# Sheet2.net
KiCad netlist of a schematic drawn in Altium Designer
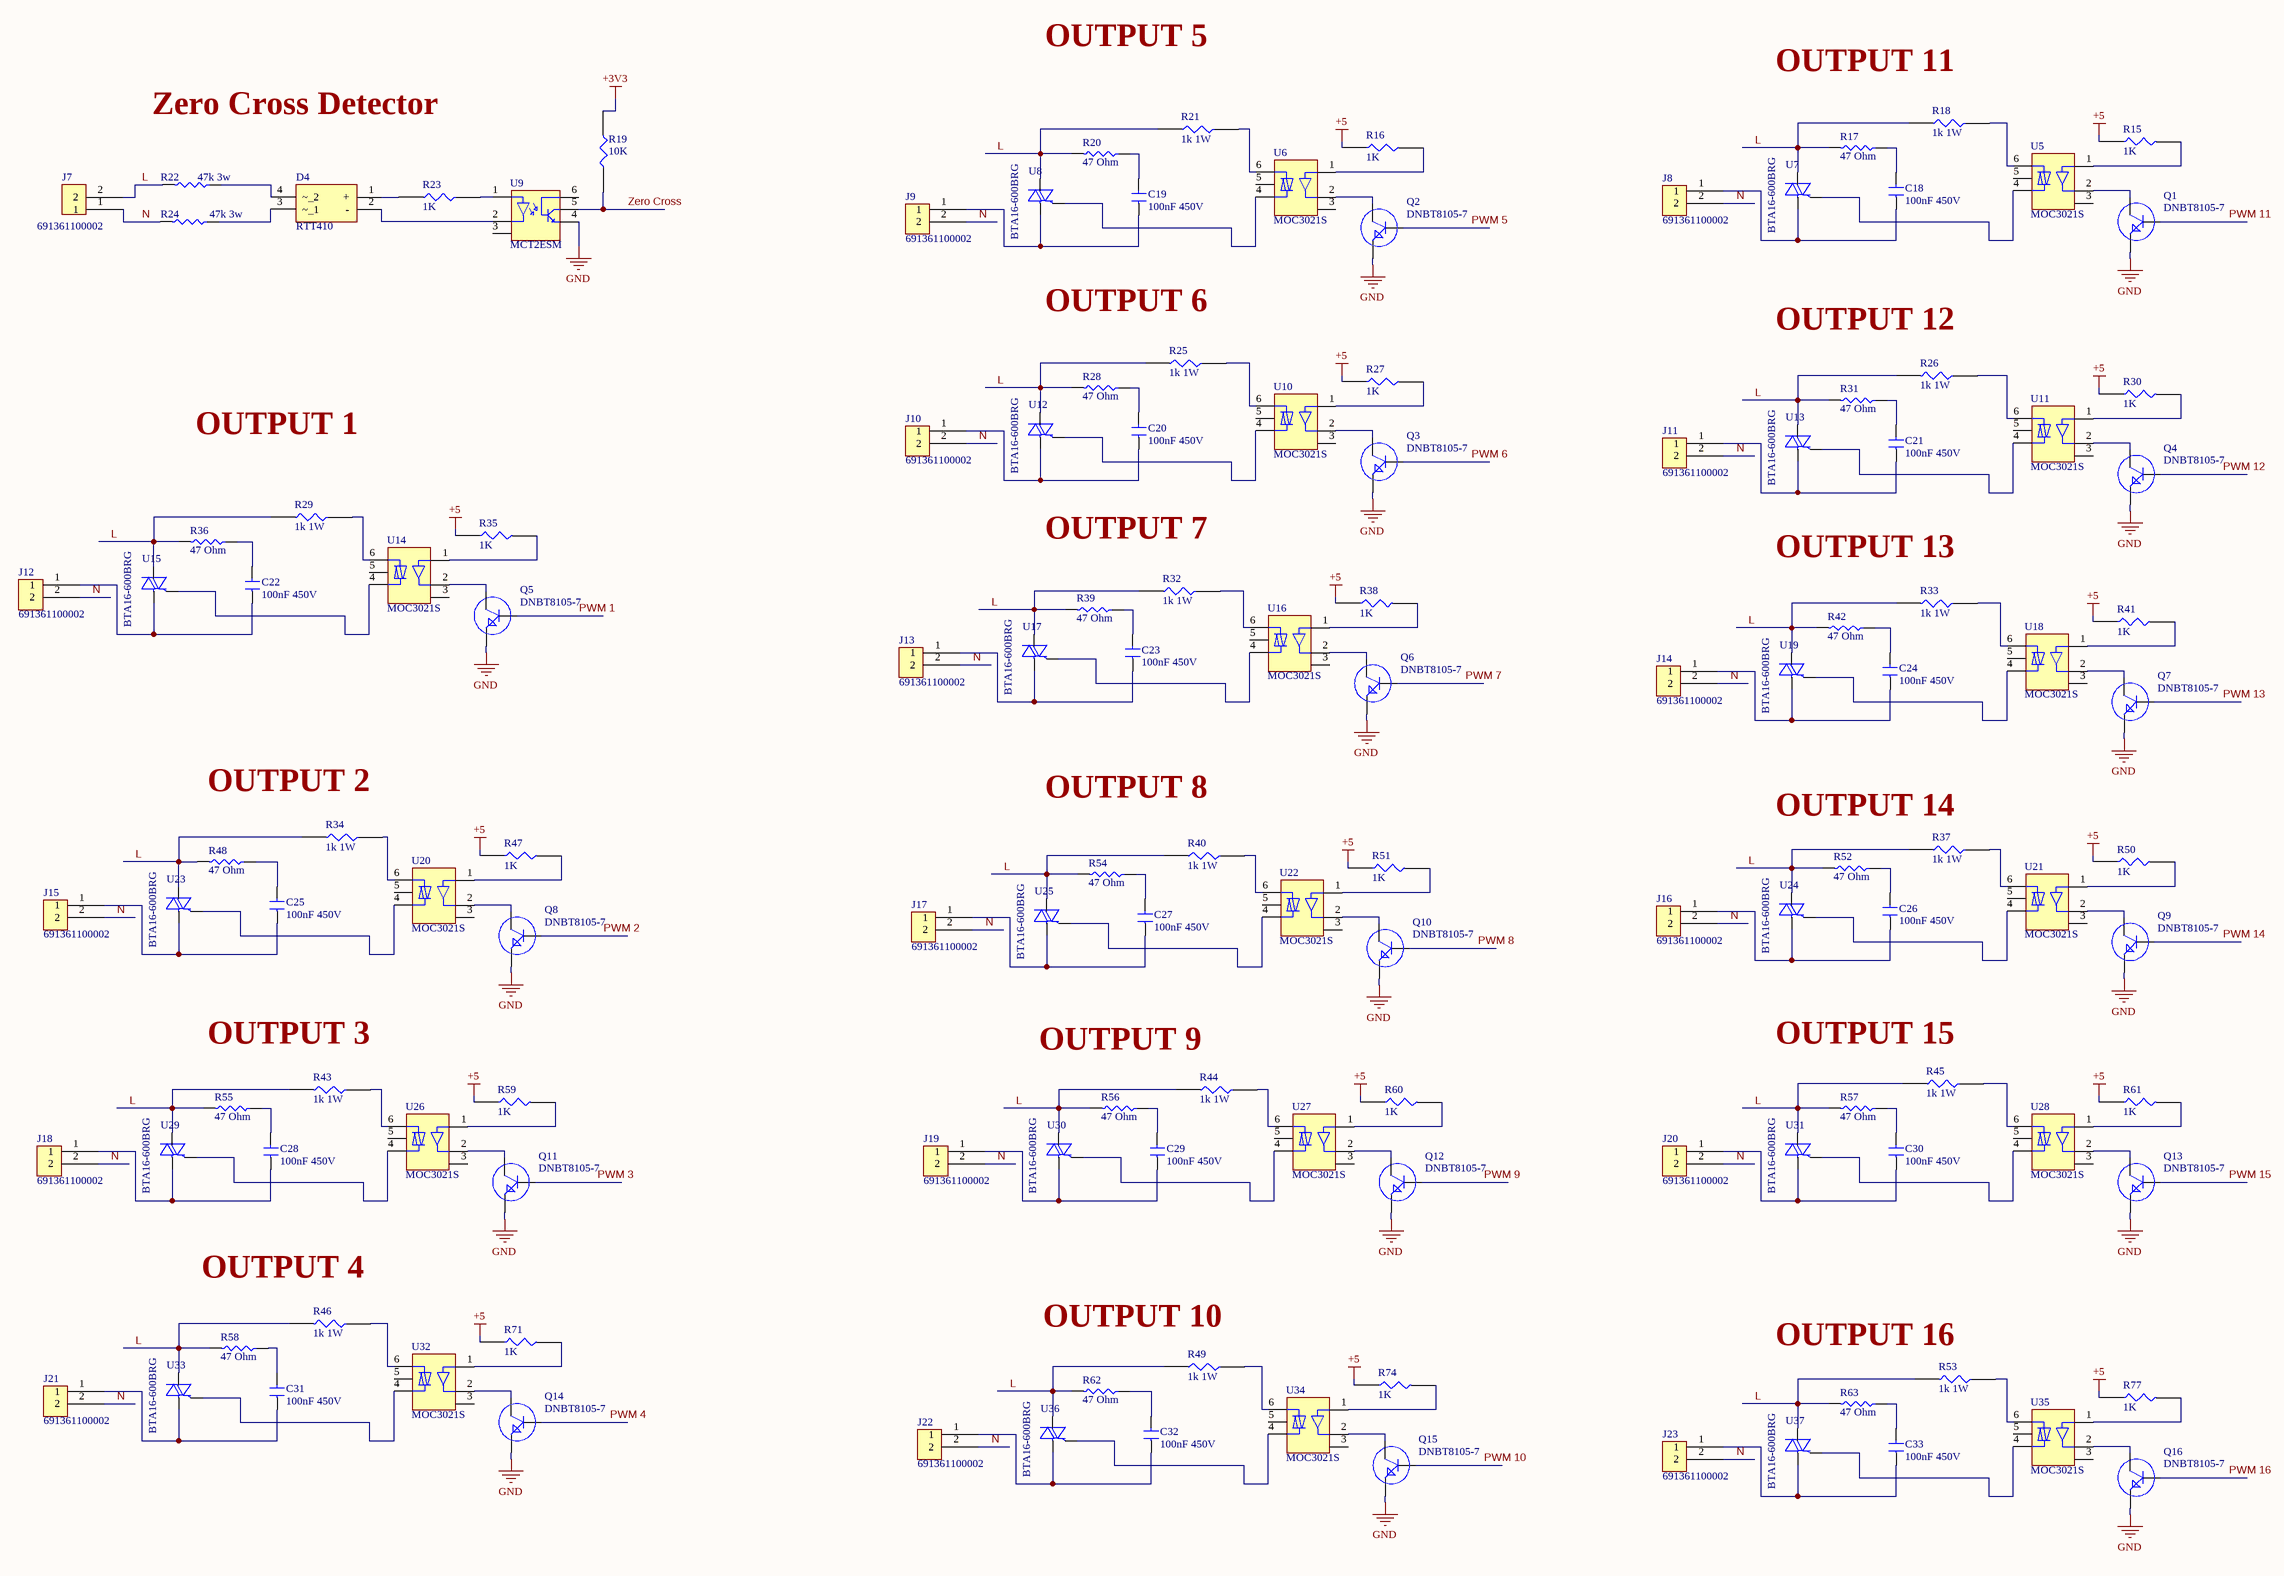
[diagram p0: Sheet2.SchDoc]

(export (version "E")
  (design (tool "Eeschema 10.0.6"))
  (components
    (comp (ref "C18")
      (value "100nF 450V")
      (footprint "CAP 1206")
      (description "Multilayer Ceramic Capacitor, 0.1 uF, 450 V, ± 10%, X7T, 1206 [3216 Metric]")
      (fields
        (field (name "MANUFACTURER") "TDK")
        (field (name "MANUFACTURER PART NUMBER") "CGA5L4X7T2W104K160AA")
      )
      (libsource (lib "Component Schematic Library V1") (part "Cap 100 nf 450V"))
    )
    (comp (ref "C19")
      (value "100nF 450V")
      (footprint "CAP 1206")
      (description "Multilayer Ceramic Capacitor, 0.1 uF, 450 V, ± 10%, X7T, 1206 [3216 Metric]")
      (fields
        (field (name "MANUFACTURER") "TDK")
        (field (name "MANUFACTURER PART NUMBER") "CGA5L4X7T2W104K160AA")
      )
      (libsource (lib "Component Schematic Library V1") (part "Cap 100 nf 450V"))
    )
    (comp (ref "C20")
      (value "100nF 450V")
      (footprint "CAP 1206")
      (description "Multilayer Ceramic Capacitor, 0.1 uF, 450 V, ± 10%, X7T, 1206 [3216 Metric]")
      (fields
        (field (name "MANUFACTURER") "TDK")
        (field (name "MANUFACTURER PART NUMBER") "CGA5L4X7T2W104K160AA")
      )
      (libsource (lib "Component Schematic Library V1") (part "Cap 100 nf 450V"))
    )
    (comp (ref "C21")
      (value "100nF 450V")
      (footprint "CAP 1206")
      (description "Multilayer Ceramic Capacitor, 0.1 uF, 450 V, ± 10%, X7T, 1206 [3216 Metric]")
      (fields
        (field (name "MANUFACTURER") "TDK")
        (field (name "MANUFACTURER PART NUMBER") "CGA5L4X7T2W104K160AA")
      )
      (libsource (lib "Component Schematic Library V1") (part "Cap 100 nf 450V"))
    )
    (comp (ref "C22")
      (value "100nF 450V")
      (footprint "CAP 1206")
      (description "Multilayer Ceramic Capacitor, 0.1 uF, 450 V, ± 10%, X7T, 1206 [3216 Metric]")
      (fields
        (field (name "MANUFACTURER") "TDK")
        (field (name "MANUFACTURER PART NUMBER") "CGA5L4X7T2W104K160AA")
      )
      (libsource (lib "Component Schematic Library V1") (part "Cap 100 nf 450V"))
    )
    (comp (ref "C23")
      (value "100nF 450V")
      (footprint "CAP 1206")
      (description "Multilayer Ceramic Capacitor, 0.1 uF, 450 V, ± 10%, X7T, 1206 [3216 Metric]")
      (fields
        (field (name "MANUFACTURER") "TDK")
        (field (name "MANUFACTURER PART NUMBER") "CGA5L4X7T2W104K160AA")
      )
      (libsource (lib "Component Schematic Library V1") (part "Cap 100 nf 450V"))
    )
    (comp (ref "C24")
      (value "100nF 450V")
      (footprint "CAP 1206")
      (description "Multilayer Ceramic Capacitor, 0.1 uF, 450 V, ± 10%, X7T, 1206 [3216 Metric]")
      (fields
        (field (name "MANUFACTURER") "TDK")
        (field (name "MANUFACTURER PART NUMBER") "CGA5L4X7T2W104K160AA")
      )
      (libsource (lib "Component Schematic Library V1") (part "Cap 100 nf 450V"))
    )
    (comp (ref "C25")
      (value "100nF 450V")
      (footprint "CAP 1206")
      (description "Multilayer Ceramic Capacitor, 0.1 uF, 450 V, ± 10%, X7T, 1206 [3216 Metric]")
      (fields
        (field (name "MANUFACTURER") "TDK")
        (field (name "MANUFACTURER PART NUMBER") "CGA5L4X7T2W104K160AA")
      )
      (libsource (lib "Component Schematic Library V1") (part "Cap 100 nf 450V"))
    )
    (comp (ref "C26")
      (value "100nF 450V")
      (footprint "CAP 1206")
      (description "Multilayer Ceramic Capacitor, 0.1 uF, 450 V, ± 10%, X7T, 1206 [3216 Metric]")
      (fields
        (field (name "MANUFACTURER") "TDK")
        (field (name "MANUFACTURER PART NUMBER") "CGA5L4X7T2W104K160AA")
      )
      (libsource (lib "Component Schematic Library V1") (part "Cap 100 nf 450V"))
    )
    (comp (ref "C27")
      (value "100nF 450V")
      (footprint "CAP 1206")
      (description "Multilayer Ceramic Capacitor, 0.1 uF, 450 V, ± 10%, X7T, 1206 [3216 Metric]")
      (fields
        (field (name "MANUFACTURER") "TDK")
        (field (name "MANUFACTURER PART NUMBER") "CGA5L4X7T2W104K160AA")
      )
      (libsource (lib "Component Schematic Library V1") (part "Cap 100 nf 450V"))
    )
    (comp (ref "C28")
      (value "100nF 450V")
      (footprint "CAP 1206")
      (description "Multilayer Ceramic Capacitor, 0.1 uF, 450 V, ± 10%, X7T, 1206 [3216 Metric]")
      (fields
        (field (name "MANUFACTURER") "TDK")
        (field (name "MANUFACTURER PART NUMBER") "CGA5L4X7T2W104K160AA")
      )
      (libsource (lib "Component Schematic Library V1") (part "Cap 100 nf 450V"))
    )
    (comp (ref "C29")
      (value "100nF 450V")
      (footprint "CAP 1206")
      (description "Multilayer Ceramic Capacitor, 0.1 uF, 450 V, ± 10%, X7T, 1206 [3216 Metric]")
      (fields
        (field (name "MANUFACTURER") "TDK")
        (field (name "MANUFACTURER PART NUMBER") "CGA5L4X7T2W104K160AA")
      )
      (libsource (lib "Component Schematic Library V1") (part "Cap 100 nf 450V"))
    )
    (comp (ref "C30")
      (value "100nF 450V")
      (footprint "CAP 1206")
      (description "Multilayer Ceramic Capacitor, 0.1 uF, 450 V, ± 10%, X7T, 1206 [3216 Metric]")
      (fields
        (field (name "MANUFACTURER") "TDK")
        (field (name "MANUFACTURER PART NUMBER") "CGA5L4X7T2W104K160AA")
      )
      (libsource (lib "Component Schematic Library V1") (part "Cap 100 nf 450V"))
    )
    (comp (ref "C31")
      (value "100nF 450V")
      (footprint "CAP 1206")
      (description "Multilayer Ceramic Capacitor, 0.1 uF, 450 V, ± 10%, X7T, 1206 [3216 Metric]")
      (fields
        (field (name "MANUFACTURER") "TDK")
        (field (name "MANUFACTURER PART NUMBER") "CGA5L4X7T2W104K160AA")
      )
      (libsource (lib "Component Schematic Library V1") (part "Cap 100 nf 450V"))
    )
    (comp (ref "C32")
      (value "100nF 450V")
      (footprint "CAP 1206")
      (description "Multilayer Ceramic Capacitor, 0.1 uF, 450 V, ± 10%, X7T, 1206 [3216 Metric]")
      (fields
        (field (name "MANUFACTURER") "TDK")
        (field (name "MANUFACTURER PART NUMBER") "CGA5L4X7T2W104K160AA")
      )
      (libsource (lib "Component Schematic Library V1") (part "Cap 100 nf 450V"))
    )
    (comp (ref "C33")
      (value "100nF 450V")
      (footprint "CAP 1206")
      (description "Multilayer Ceramic Capacitor, 0.1 uF, 450 V, ± 10%, X7T, 1206 [3216 Metric]")
      (fields
        (field (name "MANUFACTURER") "TDK")
        (field (name "MANUFACTURER PART NUMBER") "CGA5L4X7T2W104K160AA")
      )
      (libsource (lib "Component Schematic Library V1") (part "Cap 100 nf 450V"))
    )
    (comp (ref "D4")
      (value "RTT410")
      (footprint "RT410")
      (fields (field (name "MANUFACTURER") "Diodes"))
      (libsource (lib "Component Schematic Library V1") (part "RTT410"))
    )
    (comp (ref "J7")
      (value "691361100002")
      (footprint "Screw Terminal 3.5mm")
      (description "3611 Series 3.5mm Pitch Straight Pluggable Term Block; Plug; Cable Mount; 2 Way")
      (fields (field (name "MANUFACTURER") "Wurth Electronics") (field (name "VOLTAGE") "300V"))
      (libsource (lib "") (part "Screw Tarminal 3.5mm pitch_1"))
    )
    (comp (ref "J8")
      (value "691361100002")
      (footprint "Screw Terminal 3.5mm")
      (description "3611 Series 3.5mm Pitch Straight Pluggable Term Block; Plug; Cable Mount; 2 Way")
      (fields (field (name "MANUFACTURER") "Wurth Electronics") (field (name "VOLTAGE") "300V"))
      (libsource (lib "Component Schematic Library V1") (part "Screw Tarminal 3.5mm pitch"))
    )
    (comp (ref "J9")
      (value "691361100002")
      (footprint "Screw Terminal 3.5mm")
      (description "3611 Series 3.5mm Pitch Straight Pluggable Term Block; Plug; Cable Mount; 2 Way")
      (fields (field (name "MANUFACTURER") "Wurth Electronics") (field (name "VOLTAGE") "300V"))
      (libsource (lib "Component Schematic Library V1") (part "Screw Tarminal 3.5mm pitch"))
    )
    (comp (ref "J10")
      (value "691361100002")
      (footprint "Screw Terminal 3.5mm")
      (description "3611 Series 3.5mm Pitch Straight Pluggable Term Block; Plug; Cable Mount; 2 Way")
      (fields (field (name "MANUFACTURER") "Wurth Electronics") (field (name "VOLTAGE") "300V"))
      (libsource (lib "Component Schematic Library V1") (part "Screw Tarminal 3.5mm pitch"))
    )
    (comp (ref "J11")
      (value "691361100002")
      (footprint "Screw Terminal 3.5mm")
      (description "3611 Series 3.5mm Pitch Straight Pluggable Term Block; Plug; Cable Mount; 2 Way")
      (fields (field (name "MANUFACTURER") "Wurth Electronics") (field (name "VOLTAGE") "300V"))
      (libsource (lib "Component Schematic Library V1") (part "Screw Tarminal 3.5mm pitch"))
    )
    (comp (ref "J12")
      (value "691361100002")
      (footprint "Screw Terminal 3.5mm")
      (description "3611 Series 3.5mm Pitch Straight Pluggable Term Block; Plug; Cable Mount; 2 Way")
      (fields (field (name "MANUFACTURER") "Wurth Electronics") (field (name "VOLTAGE") "300V"))
      (libsource (lib "Component Schematic Library V1") (part "Screw Tarminal 3.5mm pitch"))
    )
    (comp (ref "J13")
      (value "691361100002")
      (footprint "Screw Terminal 3.5mm")
      (description "3611 Series 3.5mm Pitch Straight Pluggable Term Block; Plug; Cable Mount; 2 Way")
      (fields (field (name "MANUFACTURER") "Wurth Electronics") (field (name "VOLTAGE") "300V"))
      (libsource (lib "Component Schematic Library V1") (part "Screw Tarminal 3.5mm pitch"))
    )
    (comp (ref "J14")
      (value "691361100002")
      (footprint "Screw Terminal 3.5mm")
      (description "3611 Series 3.5mm Pitch Straight Pluggable Term Block; Plug; Cable Mount; 2 Way")
      (fields (field (name "MANUFACTURER") "Wurth Electronics") (field (name "VOLTAGE") "300V"))
      (libsource (lib "Component Schematic Library V1") (part "Screw Tarminal 3.5mm pitch"))
    )
    (comp (ref "J15")
      (value "691361100002")
      (footprint "Screw Terminal 3.5mm")
      (description "3611 Series 3.5mm Pitch Straight Pluggable Term Block; Plug; Cable Mount; 2 Way")
      (fields (field (name "MANUFACTURER") "Wurth Electronics") (field (name "VOLTAGE") "300V"))
      (libsource (lib "Component Schematic Library V1") (part "Screw Tarminal 3.5mm pitch"))
    )
    (comp (ref "J16")
      (value "691361100002")
      (footprint "Screw Terminal 3.5mm")
      (description "3611 Series 3.5mm Pitch Straight Pluggable Term Block; Plug; Cable Mount; 2 Way")
      (fields (field (name "MANUFACTURER") "Wurth Electronics") (field (name "VOLTAGE") "300V"))
      (libsource (lib "Component Schematic Library V1") (part "Screw Tarminal 3.5mm pitch"))
    )
    (comp (ref "J17")
      (value "691361100002")
      (footprint "Screw Terminal 3.5mm")
      (description "3611 Series 3.5mm Pitch Straight Pluggable Term Block; Plug; Cable Mount; 2 Way")
      (fields (field (name "MANUFACTURER") "Wurth Electronics") (field (name "VOLTAGE") "300V"))
      (libsource (lib "Component Schematic Library V1") (part "Screw Tarminal 3.5mm pitch"))
    )
    (comp (ref "J18")
      (value "691361100002")
      (footprint "Screw Terminal 3.5mm")
      (description "3611 Series 3.5mm Pitch Straight Pluggable Term Block; Plug; Cable Mount; 2 Way")
      (fields (field (name "MANUFACTURER") "Wurth Electronics") (field (name "VOLTAGE") "300V"))
      (libsource (lib "Component Schematic Library V1") (part "Screw Tarminal 3.5mm pitch"))
    )
    (comp (ref "J19")
      (value "691361100002")
      (footprint "Screw Terminal 3.5mm")
      (description "3611 Series 3.5mm Pitch Straight Pluggable Term Block; Plug; Cable Mount; 2 Way")
      (fields (field (name "MANUFACTURER") "Wurth Electronics") (field (name "VOLTAGE") "300V"))
      (libsource (lib "Component Schematic Library V1") (part "Screw Tarminal 3.5mm pitch"))
    )
    (comp (ref "J20")
      (value "691361100002")
      (footprint "Screw Terminal 3.5mm")
      (description "3611 Series 3.5mm Pitch Straight Pluggable Term Block; Plug; Cable Mount; 2 Way")
      (fields (field (name "MANUFACTURER") "Wurth Electronics") (field (name "VOLTAGE") "300V"))
      (libsource (lib "Component Schematic Library V1") (part "Screw Tarminal 3.5mm pitch"))
    )
    (comp (ref "J21")
      (value "691361100002")
      (footprint "Screw Terminal 3.5mm")
      (description "3611 Series 3.5mm Pitch Straight Pluggable Term Block; Plug; Cable Mount; 2 Way")
      (fields (field (name "MANUFACTURER") "Wurth Electronics") (field (name "VOLTAGE") "300V"))
      (libsource (lib "Component Schematic Library V1") (part "Screw Tarminal 3.5mm pitch"))
    )
    (comp (ref "J22")
      (value "691361100002")
      (footprint "Screw Terminal 3.5mm")
      (description "3611 Series 3.5mm Pitch Straight Pluggable Term Block; Plug; Cable Mount; 2 Way")
      (fields (field (name "MANUFACTURER") "Wurth Electronics") (field (name "VOLTAGE") "300V"))
      (libsource (lib "Component Schematic Library V1") (part "Screw Tarminal 3.5mm pitch"))
    )
    (comp (ref "J23")
      (value "691361100002")
      (footprint "Screw Terminal 3.5mm")
      (description "3611 Series 3.5mm Pitch Straight Pluggable Term Block; Plug; Cable Mount; 2 Way")
      (fields (field (name "MANUFACTURER") "Wurth Electronics") (field (name "VOLTAGE") "300V"))
      (libsource (lib "Component Schematic Library V1") (part "Screw Tarminal 3.5mm pitch"))
    )
    (comp (ref "Q1")
      (value "DNBT8105-7")
      (footprint "SOT 223 3")
      (description "TRANS NPN 60V 1A SOT23-3")
      (fields (field (name "MANUFACTURER") "Diodes Zetex"))
      (libsource (lib "Component Schematic Library V1") (part "NPN 1A"))
    )
    (comp (ref "Q2")
      (value "DNBT8105-7")
      (footprint "SOT 223 3")
      (description "TRANS NPN 60V 1A SOT23-3")
      (fields (field (name "MANUFACTURER") "Diodes Zetex"))
      (libsource (lib "Component Schematic Library V1") (part "NPN 1A"))
    )
    (comp (ref "Q3")
      (value "DNBT8105-7")
      (footprint "SOT 223 3")
      (description "TRANS NPN 60V 1A SOT23-3")
      (fields (field (name "MANUFACTURER") "Diodes Zetex"))
      (libsource (lib "Component Schematic Library V1") (part "NPN 1A"))
    )
    (comp (ref "Q4")
      (value "DNBT8105-7")
      (footprint "SOT 223 3")
      (description "TRANS NPN 60V 1A SOT23-3")
      (fields (field (name "MANUFACTURER") "Diodes Zetex"))
      (libsource (lib "Component Schematic Library V1") (part "NPN 1A"))
    )
    (comp (ref "Q5")
      (value "DNBT8105-7")
      (footprint "SOT 223 3")
      (description "TRANS NPN 60V 1A SOT23-3")
      (fields (field (name "MANUFACTURER") "Diodes Zetex"))
      (libsource (lib "Component Schematic Library V1") (part "NPN 1A"))
    )
    (comp (ref "Q6")
      (value "DNBT8105-7")
      (footprint "SOT 223 3")
      (description "TRANS NPN 60V 1A SOT23-3")
      (fields (field (name "MANUFACTURER") "Diodes Zetex"))
      (libsource (lib "Component Schematic Library V1") (part "NPN 1A"))
    )
    (comp (ref "Q7")
      (value "DNBT8105-7")
      (footprint "SOT 223 3")
      (description "TRANS NPN 60V 1A SOT23-3")
      (fields (field (name "MANUFACTURER") "Diodes Zetex"))
      (libsource (lib "Component Schematic Library V1") (part "NPN 1A"))
    )
    (comp (ref "Q8")
      (value "DNBT8105-7")
      (footprint "SOT 223 3")
      (description "TRANS NPN 60V 1A SOT23-3")
      (fields (field (name "MANUFACTURER") "Diodes Zetex"))
      (libsource (lib "Component Schematic Library V1") (part "NPN 1A"))
    )
    (comp (ref "Q9")
      (value "DNBT8105-7")
      (footprint "SOT 223 3")
      (description "TRANS NPN 60V 1A SOT23-3")
      (fields (field (name "MANUFACTURER") "Diodes Zetex"))
      (libsource (lib "Component Schematic Library V1") (part "NPN 1A"))
    )
    (comp (ref "Q10")
      (value "DNBT8105-7")
      (footprint "SOT 223 3")
      (description "TRANS NPN 60V 1A SOT23-3")
      (fields (field (name "MANUFACTURER") "Diodes Zetex"))
      (libsource (lib "Component Schematic Library V1") (part "NPN 1A"))
    )
    (comp (ref "Q11")
      (value "DNBT8105-7")
      (footprint "SOT 223 3")
      (description "TRANS NPN 60V 1A SOT23-3")
      (fields (field (name "MANUFACTURER") "Diodes Zetex"))
      (libsource (lib "Component Schematic Library V1") (part "NPN 1A"))
    )
    (comp (ref "Q12")
      (value "DNBT8105-7")
      (footprint "SOT 223 3")
      (description "TRANS NPN 60V 1A SOT23-3")
      (fields (field (name "MANUFACTURER") "Diodes Zetex"))
      (libsource (lib "Component Schematic Library V1") (part "NPN 1A"))
    )
    (comp (ref "Q13")
      (value "DNBT8105-7")
      (footprint "SOT 223 3")
      (description "TRANS NPN 60V 1A SOT23-3")
      (fields (field (name "MANUFACTURER") "Diodes Zetex"))
      (libsource (lib "Component Schematic Library V1") (part "NPN 1A"))
    )
    (comp (ref "Q14")
      (value "DNBT8105-7")
      (footprint "SOT 223 3")
      (description "TRANS NPN 60V 1A SOT23-3")
      (fields (field (name "MANUFACTURER") "Diodes Zetex"))
      (libsource (lib "Component Schematic Library V1") (part "NPN 1A"))
    )
    (comp (ref "Q15")
      (value "DNBT8105-7")
      (footprint "SOT 223 3")
      (description "TRANS NPN 60V 1A SOT23-3")
      (fields (field (name "MANUFACTURER") "Diodes Zetex"))
      (libsource (lib "Component Schematic Library V1") (part "NPN 1A"))
    )
    (comp (ref "Q16")
      (value "DNBT8105-7")
      (footprint "SOT 223 3")
      (description "TRANS NPN 60V 1A SOT23-3")
      (fields (field (name "MANUFACTURER") "Diodes Zetex"))
      (libsource (lib "Component Schematic Library V1") (part "NPN 1A"))
    )
    (comp (ref "R15")
      (value "1K")
      (footprint "R_0805")
      (description "贴片电阻 1000Ω ± 1.00% 0.125W ± 100ppm/℃ 0805")
      (fields
        (field (name "MANUFACTURER") "Yageo")
        (field (name "MANUFACTURER PART NUMBER") "RC0805FR-071KL")
      )
      (libsource (lib "Component Schematic Library V1") (part "RES_1_K_0805"))
    )
    (comp (ref "R16")
      (value "1K")
      (footprint "R_0805")
      (description "贴片电阻 1000Ω ± 1.00% 0.125W ± 100ppm/℃ 0805")
      (fields
        (field (name "MANUFACTURER") "Yageo")
        (field (name "MANUFACTURER PART NUMBER") "RC0805FR-071KL")
      )
      (libsource (lib "Component Schematic Library V1") (part "RES_1_K_0805"))
    )
    (comp (ref "R17")
      (value "47 Ohm")
      (footprint "R 1206")
      (description "Res Thick Film 1206 47 Ohm 1% 1/2W ±200ppm/°C Molded SMD Paper T/R")
      (fields
        (field (name "MANUFACTURER") "TE Connectivity")
        (field (name "MANUFACTURER PART NUMBER") "CRGH1206F47R")
      )
      (libsource (lib "Component Schematic Library V1") (part "Res 47 oHm 1/2 W"))
    )
    (comp (ref "R18")
      (value "1k 1W")
      (footprint "R_0805")
      (fields
        (field (name "MANUFACTURER") "TE Connectivity")
        (field (name "MANUFACTURER PART NUMBER") "RA73F2A1K0BTD")
      )
      (libsource (lib "Component Schematic Library V1") (part "Res 1K 1W"))
    )
    (comp (ref "R19")
      (value "10K")
      (footprint "R_0805")
      (description "贴片电阻 10000Ω ± 1.00% 0.125W ± 100ppm/℃ 0805")
      (fields
        (field (name "MANUFACTURER") "Yageo")
        (field (name "MANUFACTURER PART NUMBER") "RC0805FR-0710KL")
      )
      (libsource (lib "Component Schematic Library V1") (part "RES_10_K_0805"))
    )
    (comp (ref "R20")
      (value "47 Ohm")
      (footprint "R 1206")
      (description "Res Thick Film 1206 47 Ohm 1% 1/2W ±200ppm/°C Molded SMD Paper T/R")
      (fields
        (field (name "MANUFACTURER") "TE Connectivity")
        (field (name "MANUFACTURER PART NUMBER") "CRGH1206F47R")
      )
      (libsource (lib "Component Schematic Library V1") (part "Res 47 oHm 1/2 W"))
    )
    (comp (ref "R21")
      (value "1k 1W")
      (footprint "R_0805")
      (fields
        (field (name "MANUFACTURER") "TE Connectivity")
        (field (name "MANUFACTURER PART NUMBER") "RA73F2A1K0BTD")
      )
      (libsource (lib "Component Schematic Library V1") (part "Res 1K 1W"))
    )
    (comp (ref "R22")
      (value "47k 3w")
      (footprint "R 2512")
      (description "Res Thick Film 2512 47K Ohm 5% 3W ±100ppm/C Pad SMD T/R")
      (fields
        (field (name "MANUFACTURER") "TE Connectivity CGS")
        (field (name "MANUFACTURER PART NUMBER") "352247KJT")
      )
      (libsource (lib "Component Schematic Library V1") (part "RES 47K 3W SMD"))
    )
    (comp (ref "R23")
      (value "1K")
      (footprint "R_0805")
      (description "贴片电阻 1000Ω ± 1.00% 0.125W ± 100ppm/℃ 0805")
      (fields
        (field (name "MANUFACTURER") "Yageo")
        (field (name "MANUFACTURER PART NUMBER") "RC0805FR-071KL")
      )
      (libsource (lib "Component Schematic Library V1") (part "RES_1_K_0805"))
    )
    (comp (ref "R24")
      (value "47k 3w")
      (footprint "R 2512")
      (description "Res Thick Film 2512 47K Ohm 5% 3W ±100ppm/C Pad SMD T/R")
      (fields
        (field (name "MANUFACTURER") "TE Connectivity CGS")
        (field (name "MANUFACTURER PART NUMBER") "352247KJT")
      )
      (libsource (lib "Component Schematic Library V1") (part "RES 47K 3W SMD"))
    )
    (comp (ref "R25")
      (value "1k 1W")
      (footprint "R_0805")
      (fields
        (field (name "MANUFACTURER") "TE Connectivity")
        (field (name "MANUFACTURER PART NUMBER") "RA73F2A1K0BTD")
      )
      (libsource (lib "Component Schematic Library V1") (part "Res 1K 1W"))
    )
    (comp (ref "R26")
      (value "1k 1W")
      (footprint "R_0805")
      (fields
        (field (name "MANUFACTURER") "TE Connectivity")
        (field (name "MANUFACTURER PART NUMBER") "RA73F2A1K0BTD")
      )
      (libsource (lib "Component Schematic Library V1") (part "Res 1K 1W"))
    )
    (comp (ref "R27")
      (value "1K")
      (footprint "R_0805")
      (description "贴片电阻 1000Ω ± 1.00% 0.125W ± 100ppm/℃ 0805")
      (fields
        (field (name "MANUFACTURER") "Yageo")
        (field (name "MANUFACTURER PART NUMBER") "RC0805FR-071KL")
      )
      (libsource (lib "Component Schematic Library V1") (part "RES_1_K_0805"))
    )
    (comp (ref "R28")
      (value "47 Ohm")
      (footprint "R 1206")
      (description "Res Thick Film 1206 47 Ohm 1% 1/2W ±200ppm/°C Molded SMD Paper T/R")
      (fields
        (field (name "MANUFACTURER") "TE Connectivity")
        (field (name "MANUFACTURER PART NUMBER") "CRGH1206F47R")
      )
      (libsource (lib "Component Schematic Library V1") (part "Res 47 oHm 1/2 W"))
    )
    (comp (ref "R29")
      (value "1k 1W")
      (footprint "R_0805")
      (fields
        (field (name "MANUFACTURER") "TE Connectivity")
        (field (name "MANUFACTURER PART NUMBER") "RA73F2A1K0BTD")
      )
      (libsource (lib "Component Schematic Library V1") (part "Res 1K 1W"))
    )
    (comp (ref "R30")
      (value "1K")
      (footprint "R_0805")
      (description "贴片电阻 1000Ω ± 1.00% 0.125W ± 100ppm/℃ 0805")
      (fields
        (field (name "MANUFACTURER") "Yageo")
        (field (name "MANUFACTURER PART NUMBER") "RC0805FR-071KL")
      )
      (libsource (lib "Component Schematic Library V1") (part "RES_1_K_0805"))
    )
    (comp (ref "R31")
      (value "47 Ohm")
      (footprint "R 1206")
      (description "Res Thick Film 1206 47 Ohm 1% 1/2W ±200ppm/°C Molded SMD Paper T/R")
      (fields
        (field (name "MANUFACTURER") "TE Connectivity")
        (field (name "MANUFACTURER PART NUMBER") "CRGH1206F47R")
      )
      (libsource (lib "Component Schematic Library V1") (part "Res 47 oHm 1/2 W"))
    )
    (comp (ref "R32")
      (value "1k 1W")
      (footprint "R_0805")
      (fields
        (field (name "MANUFACTURER") "TE Connectivity")
        (field (name "MANUFACTURER PART NUMBER") "RA73F2A1K0BTD")
      )
      (libsource (lib "Component Schematic Library V1") (part "Res 1K 1W"))
    )
    (comp (ref "R33")
      (value "1k 1W")
      (footprint "R_0805")
      (fields
        (field (name "MANUFACTURER") "TE Connectivity")
        (field (name "MANUFACTURER PART NUMBER") "RA73F2A1K0BTD")
      )
      (libsource (lib "Component Schematic Library V1") (part "Res 1K 1W"))
    )
    (comp (ref "R34")
      (value "1k 1W")
      (footprint "R_0805")
      (fields
        (field (name "MANUFACTURER") "TE Connectivity")
        (field (name "MANUFACTURER PART NUMBER") "RA73F2A1K0BTD")
      )
      (libsource (lib "Component Schematic Library V1") (part "Res 1K 1W"))
    )
    (comp (ref "R35")
      (value "1K")
      (footprint "R_0805")
      (description "贴片电阻 1000Ω ± 1.00% 0.125W ± 100ppm/℃ 0805")
      (fields
        (field (name "MANUFACTURER") "Yageo")
        (field (name "MANUFACTURER PART NUMBER") "RC0805FR-071KL")
      )
      (libsource (lib "Component Schematic Library V1") (part "RES_1_K_0805"))
    )
    (comp (ref "R36")
      (value "47 Ohm")
      (footprint "R 1206")
      (description "Res Thick Film 1206 47 Ohm 1% 1/2W ±200ppm/°C Molded SMD Paper T/R")
      (fields
        (field (name "MANUFACTURER") "TE Connectivity")
        (field (name "MANUFACTURER PART NUMBER") "CRGH1206F47R")
      )
      (libsource (lib "Component Schematic Library V1") (part "Res 47 oHm 1/2 W"))
    )
    (comp (ref "R37")
      (value "1k 1W")
      (footprint "R_0805")
      (fields
        (field (name "MANUFACTURER") "TE Connectivity")
        (field (name "MANUFACTURER PART NUMBER") "RA73F2A1K0BTD")
      )
      (libsource (lib "Component Schematic Library V1") (part "Res 1K 1W"))
    )
    (comp (ref "R38")
      (value "1K")
      (footprint "R_0805")
      (description "贴片电阻 1000Ω ± 1.00% 0.125W ± 100ppm/℃ 0805")
      (fields
        (field (name "MANUFACTURER") "Yageo")
        (field (name "MANUFACTURER PART NUMBER") "RC0805FR-071KL")
      )
      (libsource (lib "Component Schematic Library V1") (part "RES_1_K_0805"))
    )
    (comp (ref "R39")
      (value "47 Ohm")
      (footprint "R 1206")
      (description "Res Thick Film 1206 47 Ohm 1% 1/2W ±200ppm/°C Molded SMD Paper T/R")
      (fields
        (field (name "MANUFACTURER") "TE Connectivity")
        (field (name "MANUFACTURER PART NUMBER") "CRGH1206F47R")
      )
      (libsource (lib "Component Schematic Library V1") (part "Res 47 oHm 1/2 W"))
    )
    (comp (ref "R40")
      (value "1k 1W")
      (footprint "R_0805")
      (fields
        (field (name "MANUFACTURER") "TE Connectivity")
        (field (name "MANUFACTURER PART NUMBER") "RA73F2A1K0BTD")
      )
      (libsource (lib "Component Schematic Library V1") (part "Res 1K 1W"))
    )
    (comp (ref "R41")
      (value "1K")
      (footprint "R_0805")
      (description "贴片电阻 1000Ω ± 1.00% 0.125W ± 100ppm/℃ 0805")
      (fields
        (field (name "MANUFACTURER") "Yageo")
        (field (name "MANUFACTURER PART NUMBER") "RC0805FR-071KL")
      )
      (libsource (lib "Component Schematic Library V1") (part "RES_1_K_0805"))
    )
    (comp (ref "R42")
      (value "47 Ohm")
      (footprint "R 1206")
      (description "Res Thick Film 1206 47 Ohm 1% 1/2W ±200ppm/°C Molded SMD Paper T/R")
      (fields
        (field (name "MANUFACTURER") "TE Connectivity")
        (field (name "MANUFACTURER PART NUMBER") "CRGH1206F47R")
      )
      (libsource (lib "Component Schematic Library V1") (part "Res 47 oHm 1/2 W"))
    )
    (comp (ref "R43")
      (value "1k 1W")
      (footprint "R_0805")
      (fields
        (field (name "MANUFACTURER") "TE Connectivity")
        (field (name "MANUFACTURER PART NUMBER") "RA73F2A1K0BTD")
      )
      (libsource (lib "Component Schematic Library V1") (part "Res 1K 1W"))
    )
    (comp (ref "R44")
      (value "1k 1W")
      (footprint "R_0805")
      (fields
        (field (name "MANUFACTURER") "TE Connectivity")
        (field (name "MANUFACTURER PART NUMBER") "RA73F2A1K0BTD")
      )
      (libsource (lib "Component Schematic Library V1") (part "Res 1K 1W"))
    )
    (comp (ref "R45")
      (value "1k 1W")
      (footprint "R_0805")
      (fields
        (field (name "MANUFACTURER") "TE Connectivity")
        (field (name "MANUFACTURER PART NUMBER") "RA73F2A1K0BTD")
      )
      (libsource (lib "Component Schematic Library V1") (part "Res 1K 1W"))
    )
    (comp (ref "R46")
      (value "1k 1W")
      (footprint "R_0805")
      (fields
        (field (name "MANUFACTURER") "TE Connectivity")
        (field (name "MANUFACTURER PART NUMBER") "RA73F2A1K0BTD")
      )
      (libsource (lib "Component Schematic Library V1") (part "Res 1K 1W"))
    )
    (comp (ref "R47")
      (value "1K")
      (footprint "R_0805")
      (description "贴片电阻 1000Ω ± 1.00% 0.125W ± 100ppm/℃ 0805")
      (fields
        (field (name "MANUFACTURER") "Yageo")
        (field (name "MANUFACTURER PART NUMBER") "RC0805FR-071KL")
      )
      (libsource (lib "Component Schematic Library V1") (part "RES_1_K_0805"))
    )
    (comp (ref "R48")
      (value "47 Ohm")
      (footprint "R 1206")
      (description "Res Thick Film 1206 47 Ohm 1% 1/2W ±200ppm/°C Molded SMD Paper T/R")
      (fields
        (field (name "MANUFACTURER") "TE Connectivity")
        (field (name "MANUFACTURER PART NUMBER") "CRGH1206F47R")
      )
      (libsource (lib "Component Schematic Library V1") (part "Res 47 oHm 1/2 W"))
    )
    (comp (ref "R49")
      (value "1k 1W")
      (footprint "R_0805")
      (fields
        (field (name "MANUFACTURER") "TE Connectivity")
        (field (name "MANUFACTURER PART NUMBER") "RA73F2A1K0BTD")
      )
      (libsource (lib "Component Schematic Library V1") (part "Res 1K 1W"))
    )
    (comp (ref "R50")
      (value "1K")
      (footprint "R_0805")
      (description "贴片电阻 1000Ω ± 1.00% 0.125W ± 100ppm/℃ 0805")
      (fields
        (field (name "MANUFACTURER") "Yageo")
        (field (name "MANUFACTURER PART NUMBER") "RC0805FR-071KL")
      )
      (libsource (lib "Component Schematic Library V1") (part "RES_1_K_0805"))
    )
    (comp (ref "R51")
      (value "1K")
      (footprint "R_0805")
      (description "贴片电阻 1000Ω ± 1.00% 0.125W ± 100ppm/℃ 0805")
      (fields
        (field (name "MANUFACTURER") "Yageo")
        (field (name "MANUFACTURER PART NUMBER") "RC0805FR-071KL")
      )
      (libsource (lib "Component Schematic Library V1") (part "RES_1_K_0805"))
    )
    (comp (ref "R52")
      (value "47 Ohm")
      (footprint "R 1206")
      (description "Res Thick Film 1206 47 Ohm 1% 1/2W ±200ppm/°C Molded SMD Paper T/R")
      (fields
        (field (name "MANUFACTURER") "TE Connectivity")
        (field (name "MANUFACTURER PART NUMBER") "CRGH1206F47R")
      )
      (libsource (lib "Component Schematic Library V1") (part "Res 47 oHm 1/2 W"))
    )
    (comp (ref "R53")
      (value "1k 1W")
      (footprint "R_0805")
      (fields
        (field (name "MANUFACTURER") "TE Connectivity")
        (field (name "MANUFACTURER PART NUMBER") "RA73F2A1K0BTD")
      )
      (libsource (lib "Component Schematic Library V1") (part "Res 1K 1W"))
    )
    (comp (ref "R54")
      (value "47 Ohm")
      (footprint "R 1206")
      (description "Res Thick Film 1206 47 Ohm 1% 1/2W ±200ppm/°C Molded SMD Paper T/R")
      (fields
        (field (name "MANUFACTURER") "TE Connectivity")
        (field (name "MANUFACTURER PART NUMBER") "CRGH1206F47R")
      )
      (libsource (lib "Component Schematic Library V1") (part "Res 47 oHm 1/2 W"))
    )
    (comp (ref "R55")
      (value "47 Ohm")
      (footprint "R 1206")
      (description "Res Thick Film 1206 47 Ohm 1% 1/2W ±200ppm/°C Molded SMD Paper T/R")
      (fields
        (field (name "MANUFACTURER") "TE Connectivity")
        (field (name "MANUFACTURER PART NUMBER") "CRGH1206F47R")
      )
      (libsource (lib "Component Schematic Library V1") (part "Res 47 oHm 1/2 W"))
    )
    (comp (ref "R56")
      (value "47 Ohm")
      (footprint "R 1206")
      (description "Res Thick Film 1206 47 Ohm 1% 1/2W ±200ppm/°C Molded SMD Paper T/R")
      (fields
        (field (name "MANUFACTURER") "TE Connectivity")
        (field (name "MANUFACTURER PART NUMBER") "CRGH1206F47R")
      )
      (libsource (lib "Component Schematic Library V1") (part "Res 47 oHm 1/2 W"))
    )
    (comp (ref "R57")
      (value "47 Ohm")
      (footprint "R 1206")
      (description "Res Thick Film 1206 47 Ohm 1% 1/2W ±200ppm/°C Molded SMD Paper T/R")
      (fields
        (field (name "MANUFACTURER") "TE Connectivity")
        (field (name "MANUFACTURER PART NUMBER") "CRGH1206F47R")
      )
      (libsource (lib "Component Schematic Library V1") (part "Res 47 oHm 1/2 W"))
    )
    (comp (ref "R58")
      (value "47 Ohm")
      (footprint "R 1206")
      (description "Res Thick Film 1206 47 Ohm 1% 1/2W ±200ppm/°C Molded SMD Paper T/R")
      (fields
        (field (name "MANUFACTURER") "TE Connectivity")
        (field (name "MANUFACTURER PART NUMBER") "CRGH1206F47R")
      )
      (libsource (lib "Component Schematic Library V1") (part "Res 47 oHm 1/2 W"))
    )
    (comp (ref "R59")
      (value "1K")
      (footprint "R_0805")
      (description "贴片电阻 1000Ω ± 1.00% 0.125W ± 100ppm/℃ 0805")
      (fields
        (field (name "MANUFACTURER") "Yageo")
        (field (name "MANUFACTURER PART NUMBER") "RC0805FR-071KL")
      )
      (libsource (lib "Component Schematic Library V1") (part "RES_1_K_0805"))
    )
    (comp (ref "R60")
      (value "1K")
      (footprint "R_0805")
      (description "贴片电阻 1000Ω ± 1.00% 0.125W ± 100ppm/℃ 0805")
      (fields
        (field (name "MANUFACTURER") "Yageo")
        (field (name "MANUFACTURER PART NUMBER") "RC0805FR-071KL")
      )
      (libsource (lib "Component Schematic Library V1") (part "RES_1_K_0805"))
    )
    (comp (ref "R61")
      (value "1K")
      (footprint "R_0805")
      (description "贴片电阻 1000Ω ± 1.00% 0.125W ± 100ppm/℃ 0805")
      (fields
        (field (name "MANUFACTURER") "Yageo")
        (field (name "MANUFACTURER PART NUMBER") "RC0805FR-071KL")
      )
      (libsource (lib "Component Schematic Library V1") (part "RES_1_K_0805"))
    )
    (comp (ref "R62")
      (value "47 Ohm")
      (footprint "R 1206")
      (description "Res Thick Film 1206 47 Ohm 1% 1/2W ±200ppm/°C Molded SMD Paper T/R")
      (fields
        (field (name "MANUFACTURER") "TE Connectivity")
        (field (name "MANUFACTURER PART NUMBER") "CRGH1206F47R")
      )
      (libsource (lib "Component Schematic Library V1") (part "Res 47 oHm 1/2 W"))
    )
    (comp (ref "R63")
      (value "47 Ohm")
      (footprint "R 1206")
      (description "Res Thick Film 1206 47 Ohm 1% 1/2W ±200ppm/°C Molded SMD Paper T/R")
      (fields
        (field (name "MANUFACTURER") "TE Connectivity")
        (field (name "MANUFACTURER PART NUMBER") "CRGH1206F47R")
      )
      (libsource (lib "Component Schematic Library V1") (part "Res 47 oHm 1/2 W"))
    )
    (comp (ref "R71")
      (value "1K")
      (footprint "R_0805")
      (description "贴片电阻 1000Ω ± 1.00% 0.125W ± 100ppm/℃ 0805")
      (fields
        (field (name "MANUFACTURER") "Yageo")
        (field (name "MANUFACTURER PART NUMBER") "RC0805FR-071KL")
      )
      (libsource (lib "Component Schematic Library V1") (part "RES_1_K_0805"))
    )
    (comp (ref "R74")
      (value "1K")
      (footprint "R_0805")
      (description "贴片电阻 1000Ω ± 1.00% 0.125W ± 100ppm/℃ 0805")
      (fields
        (field (name "MANUFACTURER") "Yageo")
        (field (name "MANUFACTURER PART NUMBER") "RC0805FR-071KL")
      )
      (libsource (lib "Component Schematic Library V1") (part "RES_1_K_0805"))
    )
    (comp (ref "R77")
      (value "1K")
      (footprint "R_0805")
      (description "贴片电阻 1000Ω ± 1.00% 0.125W ± 100ppm/℃ 0805")
      (fields
        (field (name "MANUFACTURER") "Yageo")
        (field (name "MANUFACTURER PART NUMBER") "RC0805FR-071KL")
      )
      (libsource (lib "Component Schematic Library V1") (part "RES_1_K_0805"))
    )
    (comp (ref "U5")
      (value "MOC3021S")
      (footprint "SMD 6")
      (description "MOC302x Series 1 Channel 400 V 5000 Vrms Surface Mount Triac Optocoupler - SMD-6")
      (fields (field (name "MANUFACTURER") "Vishay Lite-On"))
      (libsource (lib "Component Schematic Library V1") (part "MOC3021S"))
    )
    (comp (ref "U6")
      (value "MOC3021S")
      (footprint "SMD 6")
      (description "MOC302x Series 1 Channel 400 V 5000 Vrms Surface Mount Triac Optocoupler - SMD-6")
      (fields (field (name "MANUFACTURER") "Vishay Lite-On"))
      (libsource (lib "Component Schematic Library V1") (part "MOC3021S"))
    )
    (comp (ref "U7")
      (value "BTA16-600BRG")
      (footprint "BAT16")
      (description "TRIAC Standard 600V 16A Through Hole TO-220AB")
      (libsource (lib "Component Schematic Library V1") (part "Triac"))
    )
    (comp (ref "U8")
      (value "BTA16-600BRG")
      (footprint "BAT16")
      (description "TRIAC Standard 600V 16A Through Hole TO-220AB")
      (libsource (lib "Component Schematic Library V1") (part "Triac"))
    )
    (comp (ref "U9")
      (value "MCT2ESM")
      (footprint "SMD 6")
      (description "DC-IN 1-CH Transistor With Base DC-OUT 6-Pin PDIP SMD")
      (fields (field (name "MANUFACTURER") "ON Semiconductor / Fairchild"))
      (libsource (lib "Component Schematic Library V1") (part "MCT2ESM"))
    )
    (comp (ref "U10")
      (value "MOC3021S")
      (footprint "SMD 6")
      (description "MOC302x Series 1 Channel 400 V 5000 Vrms Surface Mount Triac Optocoupler - SMD-6")
      (fields (field (name "MANUFACTURER") "Vishay Lite-On"))
      (libsource (lib "Component Schematic Library V1") (part "MOC3021S"))
    )
    (comp (ref "U11")
      (value "MOC3021S")
      (footprint "SMD 6")
      (description "MOC302x Series 1 Channel 400 V 5000 Vrms Surface Mount Triac Optocoupler - SMD-6")
      (fields (field (name "MANUFACTURER") "Vishay Lite-On"))
      (libsource (lib "Component Schematic Library V1") (part "MOC3021S"))
    )
    (comp (ref "U12")
      (value "BTA16-600BRG")
      (footprint "BAT16")
      (description "TRIAC Standard 600V 16A Through Hole TO-220AB")
      (libsource (lib "Component Schematic Library V1") (part "Triac"))
    )
    (comp (ref "U13")
      (value "BTA16-600BRG")
      (footprint "BAT16")
      (description "TRIAC Standard 600V 16A Through Hole TO-220AB")
      (libsource (lib "Component Schematic Library V1") (part "Triac"))
    )
    (comp (ref "U14")
      (value "MOC3021S")
      (footprint "SMD 6")
      (description "MOC302x Series 1 Channel 400 V 5000 Vrms Surface Mount Triac Optocoupler - SMD-6")
      (fields (field (name "MANUFACTURER") "Vishay Lite-On"))
      (libsource (lib "Component Schematic Library V1") (part "MOC3021S"))
    )
    (comp (ref "U15")
      (value "BTA16-600BRG")
      (footprint "BAT16")
      (description "TRIAC Standard 600V 16A Through Hole TO-220AB")
      (libsource (lib "Component Schematic Library V1") (part "Triac"))
    )
    (comp (ref "U16")
      (value "MOC3021S")
      (footprint "SMD 6")
      (description "MOC302x Series 1 Channel 400 V 5000 Vrms Surface Mount Triac Optocoupler - SMD-6")
      (fields (field (name "MANUFACTURER") "Vishay Lite-On"))
      (libsource (lib "Component Schematic Library V1") (part "MOC3021S"))
    )
    (comp (ref "U17")
      (value "BTA16-600BRG")
      (footprint "BAT16")
      (description "TRIAC Standard 600V 16A Through Hole TO-220AB")
      (libsource (lib "Component Schematic Library V1") (part "Triac"))
    )
    (comp (ref "U18")
      (value "MOC3021S")
      (footprint "SMD 6")
      (description "MOC302x Series 1 Channel 400 V 5000 Vrms Surface Mount Triac Optocoupler - SMD-6")
      (fields (field (name "MANUFACTURER") "Vishay Lite-On"))
      (libsource (lib "Component Schematic Library V1") (part "MOC3021S"))
    )
    (comp (ref "U19")
      (value "BTA16-600BRG")
      (footprint "BAT16")
      (description "TRIAC Standard 600V 16A Through Hole TO-220AB")
      (libsource (lib "Component Schematic Library V1") (part "Triac"))
    )
    (comp (ref "U20")
      (value "MOC3021S")
      (footprint "SMD 6")
      (description "MOC302x Series 1 Channel 400 V 5000 Vrms Surface Mount Triac Optocoupler - SMD-6")
      (fields (field (name "MANUFACTURER") "Vishay Lite-On"))
      (libsource (lib "Component Schematic Library V1") (part "MOC3021S"))
    )
    (comp (ref "U21")
      (value "MOC3021S")
      (footprint "SMD 6")
      (description "MOC302x Series 1 Channel 400 V 5000 Vrms Surface Mount Triac Optocoupler - SMD-6")
      (fields (field (name "MANUFACTURER") "Vishay Lite-On"))
      (libsource (lib "Component Schematic Library V1") (part "MOC3021S"))
    )
    (comp (ref "U22")
      (value "MOC3021S")
      (footprint "SMD 6")
      (description "MOC302x Series 1 Channel 400 V 5000 Vrms Surface Mount Triac Optocoupler - SMD-6")
      (fields (field (name "MANUFACTURER") "Vishay Lite-On"))
      (libsource (lib "Component Schematic Library V1") (part "MOC3021S"))
    )
    (comp (ref "U23")
      (value "BTA16-600BRG")
      (footprint "BAT16")
      (description "TRIAC Standard 600V 16A Through Hole TO-220AB")
      (libsource (lib "Component Schematic Library V1") (part "Triac"))
    )
    (comp (ref "U24")
      (value "BTA16-600BRG")
      (footprint "BAT16")
      (description "TRIAC Standard 600V 16A Through Hole TO-220AB")
      (libsource (lib "Component Schematic Library V1") (part "Triac"))
    )
    (comp (ref "U25")
      (value "BTA16-600BRG")
      (footprint "BAT16")
      (description "TRIAC Standard 600V 16A Through Hole TO-220AB")
      (libsource (lib "Component Schematic Library V1") (part "Triac"))
    )
    (comp (ref "U26")
      (value "MOC3021S")
      (footprint "SMD 6")
      (description "MOC302x Series 1 Channel 400 V 5000 Vrms Surface Mount Triac Optocoupler - SMD-6")
      (fields (field (name "MANUFACTURER") "Vishay Lite-On"))
      (libsource (lib "Component Schematic Library V1") (part "MOC3021S"))
    )
    (comp (ref "U27")
      (value "MOC3021S")
      (footprint "SMD 6")
      (description "MOC302x Series 1 Channel 400 V 5000 Vrms Surface Mount Triac Optocoupler - SMD-6")
      (fields (field (name "MANUFACTURER") "Vishay Lite-On"))
      (libsource (lib "Component Schematic Library V1") (part "MOC3021S"))
    )
    (comp (ref "U28")
      (value "MOC3021S")
      (footprint "SMD 6")
      (description "MOC302x Series 1 Channel 400 V 5000 Vrms Surface Mount Triac Optocoupler - SMD-6")
      (fields (field (name "MANUFACTURER") "Vishay Lite-On"))
      (libsource (lib "Component Schematic Library V1") (part "MOC3021S"))
    )
    (comp (ref "U29")
      (value "BTA16-600BRG")
      (footprint "BAT16")
      (description "TRIAC Standard 600V 16A Through Hole TO-220AB")
      (libsource (lib "Component Schematic Library V1") (part "Triac"))
    )
    (comp (ref "U30")
      (value "BTA16-600BRG")
      (footprint "BAT16")
      (description "TRIAC Standard 600V 16A Through Hole TO-220AB")
      (libsource (lib "Component Schematic Library V1") (part "Triac"))
    )
    (comp (ref "U31")
      (value "BTA16-600BRG")
      (footprint "BAT16")
      (description "TRIAC Standard 600V 16A Through Hole TO-220AB")
      (libsource (lib "Component Schematic Library V1") (part "Triac"))
    )
    (comp (ref "U32")
      (value "MOC3021S")
      (footprint "SMD 6")
      (description "MOC302x Series 1 Channel 400 V 5000 Vrms Surface Mount Triac Optocoupler - SMD-6")
      (fields (field (name "MANUFACTURER") "Vishay Lite-On"))
      (libsource (lib "Component Schematic Library V1") (part "MOC3021S"))
    )
    (comp (ref "U33")
      (value "BTA16-600BRG")
      (footprint "BAT16")
      (description "TRIAC Standard 600V 16A Through Hole TO-220AB")
      (libsource (lib "Component Schematic Library V1") (part "Triac"))
    )
    (comp (ref "U34")
      (value "MOC3021S")
      (footprint "SMD 6")
      (description "MOC302x Series 1 Channel 400 V 5000 Vrms Surface Mount Triac Optocoupler - SMD-6")
      (fields (field (name "MANUFACTURER") "Vishay Lite-On"))
      (libsource (lib "Component Schematic Library V1") (part "MOC3021S"))
    )
    (comp (ref "U35")
      (value "MOC3021S")
      (footprint "SMD 6")
      (description "MOC302x Series 1 Channel 400 V 5000 Vrms Surface Mount Triac Optocoupler - SMD-6")
      (fields (field (name "MANUFACTURER") "Vishay Lite-On"))
      (libsource (lib "Component Schematic Library V1") (part "MOC3021S"))
    )
    (comp (ref "U36")
      (value "BTA16-600BRG")
      (footprint "BAT16")
      (description "TRIAC Standard 600V 16A Through Hole TO-220AB")
      (libsource (lib "Component Schematic Library V1") (part "Triac"))
    )
    (comp (ref "U37")
      (value "BTA16-600BRG")
      (footprint "BAT16")
      (description "TRIAC Standard 600V 16A Through Hole TO-220AB")
      (libsource (lib "Component Schematic Library V1") (part "Triac"))
    )
  )
  (nets
    (net (code "1") (name "+3V3") (class "Default")
      (node (ref "R19") (pin "1") (pinfunction "2_1") (pintype "passive"))
    )
    (net (code "2") (name "+5") (class "Default")
      (node (ref "R15") (pin "2") (pinfunction "3_2") (pintype "passive"))
      (node (ref "R16") (pin "2") (pinfunction "3_2") (pintype "passive"))
      (node (ref "R27") (pin "2") (pinfunction "3_2") (pintype "passive"))
      (node (ref "R30") (pin "2") (pinfunction "3_2") (pintype "passive"))
      (node (ref "R35") (pin "2") (pinfunction "3_2") (pintype "passive"))
      (node (ref "R38") (pin "2") (pinfunction "3_2") (pintype "passive"))
      (node (ref "R41") (pin "2") (pinfunction "3_2") (pintype "passive"))
      (node (ref "R47") (pin "2") (pinfunction "3_2") (pintype "passive"))
      (node (ref "R50") (pin "2") (pinfunction "3_2") (pintype "passive"))
      (node (ref "R51") (pin "2") (pinfunction "3_2") (pintype "passive"))
      (node (ref "R59") (pin "2") (pinfunction "3_2") (pintype "passive"))
      (node (ref "R60") (pin "2") (pinfunction "3_2") (pintype "passive"))
      (node (ref "R61") (pin "2") (pinfunction "3_2") (pintype "passive"))
      (node (ref "R71") (pin "2") (pinfunction "3_2") (pintype "passive"))
      (node (ref "R74") (pin "2") (pinfunction "3_2") (pintype "passive"))
      (node (ref "R77") (pin "2") (pinfunction "3_2") (pintype "passive"))
    )
    (net (code "3") (name "/L") (class "Default")
      (node (ref "J7") (pin "2") (pinfunction "2_2") (pintype "passive"))
      (node (ref "R17") (pin "1") (pinfunction "1_1") (pintype "passive"))
      (node (ref "R18") (pin "1") (pinfunction "2_1") (pintype "passive"))
      (node (ref "R20") (pin "1") (pinfunction "1_1") (pintype "passive"))
      (node (ref "R21") (pin "1") (pinfunction "2_1") (pintype "passive"))
      (node (ref "R22") (pin "1") (pinfunction "1_1") (pintype "passive"))
      (node (ref "R25") (pin "1") (pinfunction "2_1") (pintype "passive"))
      (node (ref "R26") (pin "1") (pinfunction "2_1") (pintype "passive"))
      (node (ref "R28") (pin "1") (pinfunction "1_1") (pintype "passive"))
      (node (ref "R29") (pin "1") (pinfunction "2_1") (pintype "passive"))
      (node (ref "R31") (pin "1") (pinfunction "1_1") (pintype "passive"))
      (node (ref "R32") (pin "1") (pinfunction "2_1") (pintype "passive"))
      (node (ref "R33") (pin "1") (pinfunction "2_1") (pintype "passive"))
      (node (ref "R34") (pin "1") (pinfunction "2_1") (pintype "passive"))
      (node (ref "R36") (pin "1") (pinfunction "1_1") (pintype "passive"))
      (node (ref "R37") (pin "1") (pinfunction "2_1") (pintype "passive"))
      (node (ref "R39") (pin "1") (pinfunction "1_1") (pintype "passive"))
      (node (ref "R40") (pin "1") (pinfunction "2_1") (pintype "passive"))
      (node (ref "R42") (pin "1") (pinfunction "1_1") (pintype "passive"))
      (node (ref "R43") (pin "1") (pinfunction "2_1") (pintype "passive"))
      (node (ref "R44") (pin "1") (pinfunction "2_1") (pintype "passive"))
      (node (ref "R45") (pin "1") (pinfunction "2_1") (pintype "passive"))
      (node (ref "R46") (pin "1") (pinfunction "2_1") (pintype "passive"))
      (node (ref "R48") (pin "1") (pinfunction "1_1") (pintype "passive"))
      (node (ref "R49") (pin "1") (pinfunction "2_1") (pintype "passive"))
      (node (ref "R52") (pin "1") (pinfunction "1_1") (pintype "passive"))
      (node (ref "R53") (pin "1") (pinfunction "2_1") (pintype "passive"))
      (node (ref "R54") (pin "1") (pinfunction "1_1") (pintype "passive"))
      (node (ref "R55") (pin "1") (pinfunction "1_1") (pintype "passive"))
      (node (ref "R56") (pin "1") (pinfunction "1_1") (pintype "passive"))
      (node (ref "R57") (pin "1") (pinfunction "1_1") (pintype "passive"))
      (node (ref "R58") (pin "1") (pinfunction "1_1") (pintype "passive"))
      (node (ref "R62") (pin "1") (pinfunction "1_1") (pintype "passive"))
      (node (ref "R63") (pin "1") (pinfunction "1_1") (pintype "passive"))
      (node (ref "U12") (pin "2") (pinfunction "A2_2") (pintype "passive"))
      (node (ref "U13") (pin "2") (pinfunction "A2_2") (pintype "passive"))
      (node (ref "U15") (pin "2") (pinfunction "A2_2") (pintype "passive"))
      (node (ref "U17") (pin "2") (pinfunction "A2_2") (pintype "passive"))
      (node (ref "U19") (pin "2") (pinfunction "A2_2") (pintype "passive"))
      (node (ref "U23") (pin "2") (pinfunction "A2_2") (pintype "passive"))
      (node (ref "U24") (pin "2") (pinfunction "A2_2") (pintype "passive"))
      (node (ref "U25") (pin "2") (pinfunction "A2_2") (pintype "passive"))
      (node (ref "U29") (pin "2") (pinfunction "A2_2") (pintype "passive"))
      (node (ref "U30") (pin "2") (pinfunction "A2_2") (pintype "passive"))
      (node (ref "U31") (pin "2") (pinfunction "A2_2") (pintype "passive"))
      (node (ref "U33") (pin "2") (pinfunction "A2_2") (pintype "passive"))
      (node (ref "U36") (pin "2") (pinfunction "A2_2") (pintype "passive"))
      (node (ref "U37") (pin "2") (pinfunction "A2_2") (pintype "passive"))
      (node (ref "U7") (pin "2") (pinfunction "A2_2") (pintype "passive"))
      (node (ref "U8") (pin "2") (pinfunction "A2_2") (pintype "passive"))
    )
    (net (code "4") (name "/N") (class "Default")
      (node (ref "J10") (pin "2") (pinfunction "2_2") (pintype "passive"))
      (node (ref "J11") (pin "2") (pinfunction "2_2") (pintype "passive"))
      (node (ref "J12") (pin "2") (pinfunction "2_2") (pintype "passive"))
      (node (ref "J13") (pin "2") (pinfunction "2_2") (pintype "passive"))
      (node (ref "J14") (pin "2") (pinfunction "2_2") (pintype "passive"))
      (node (ref "J15") (pin "2") (pinfunction "2_2") (pintype "passive"))
      (node (ref "J16") (pin "2") (pinfunction "2_2") (pintype "passive"))
      (node (ref "J17") (pin "2") (pinfunction "2_2") (pintype "passive"))
      (node (ref "J18") (pin "2") (pinfunction "2_2") (pintype "passive"))
      (node (ref "J19") (pin "2") (pinfunction "2_2") (pintype "passive"))
      (node (ref "J20") (pin "2") (pinfunction "2_2") (pintype "passive"))
      (node (ref "J21") (pin "2") (pinfunction "2_2") (pintype "passive"))
      (node (ref "J22") (pin "2") (pinfunction "2_2") (pintype "passive"))
      (node (ref "J23") (pin "2") (pinfunction "2_2") (pintype "passive"))
      (node (ref "J7") (pin "1") (pinfunction "1_1") (pintype "passive"))
      (node (ref "J8") (pin "2") (pinfunction "2_2") (pintype "passive"))
      (node (ref "J9") (pin "2") (pinfunction "2_2") (pintype "passive"))
      (node (ref "R24") (pin "1") (pinfunction "1_1") (pintype "passive"))
    )
    (net (code "5") (name "/PWM 1") (class "Default")
      (node (ref "Q5") (pin "1") (pinfunction "1_1") (pintype "passive"))
    )
    (net (code "6") (name "/PWM 2") (class "Default")
      (node (ref "Q8") (pin "1") (pinfunction "1_1") (pintype "passive"))
    )
    (net (code "7") (name "/PWM 3") (class "Default")
      (node (ref "Q11") (pin "1") (pinfunction "1_1") (pintype "passive"))
    )
    (net (code "8") (name "/PWM 4") (class "Default")
      (node (ref "Q14") (pin "1") (pinfunction "1_1") (pintype "passive"))
    )
    (net (code "9") (name "/PWM 5") (class "Default")
      (node (ref "Q2") (pin "1") (pinfunction "1_1") (pintype "passive"))
    )
    (net (code "10") (name "/PWM 6") (class "Default")
      (node (ref "Q3") (pin "1") (pinfunction "1_1") (pintype "passive"))
    )
    (net (code "11") (name "/PWM 7") (class "Default")
      (node (ref "Q6") (pin "1") (pinfunction "1_1") (pintype "passive"))
    )
    (net (code "12") (name "/PWM 8") (class "Default")
      (node (ref "Q10") (pin "1") (pinfunction "1_1") (pintype "passive"))
    )
    (net (code "13") (name "/PWM 9") (class "Default")
      (node (ref "Q12") (pin "1") (pinfunction "1_1") (pintype "passive"))
    )
    (net (code "14") (name "/PWM 10") (class "Default")
      (node (ref "Q15") (pin "1") (pinfunction "1_1") (pintype "passive"))
    )
    (net (code "15") (name "/PWM 11") (class "Default")
      (node (ref "Q1") (pin "1") (pinfunction "1_1") (pintype "passive"))
    )
    (net (code "16") (name "/PWM 12") (class "Default")
      (node (ref "Q4") (pin "1") (pinfunction "1_1") (pintype "passive"))
    )
    (net (code "17") (name "/PWM 13") (class "Default")
      (node (ref "Q7") (pin "1") (pinfunction "1_1") (pintype "passive"))
    )
    (net (code "18") (name "/PWM 14") (class "Default")
      (node (ref "Q9") (pin "1") (pinfunction "1_1") (pintype "passive"))
    )
    (net (code "19") (name "/PWM 15") (class "Default")
      (node (ref "Q13") (pin "1") (pinfunction "1_1") (pintype "passive"))
    )
    (net (code "20") (name "/PWM 16") (class "Default")
      (node (ref "Q16") (pin "1") (pinfunction "1_1") (pintype "passive"))
    )
    (net (code "21") (name "/Zero Cross") (class "Default")
      (node (ref "R19") (pin "2") (pinfunction "3_2") (pintype "passive"))
      (node (ref "U9") (pin "5") (pinfunction "5_5") (pintype "passive"))
    )
    (net (code "22") (name "GND") (class "Default")
      (node (ref "Q1") (pin "2") (pinfunction "2_2") (pintype "passive"))
      (node (ref "Q10") (pin "2") (pinfunction "2_2") (pintype "passive"))
      (node (ref "Q11") (pin "2") (pinfunction "2_2") (pintype "passive"))
      (node (ref "Q12") (pin "2") (pinfunction "2_2") (pintype "passive"))
      (node (ref "Q13") (pin "2") (pinfunction "2_2") (pintype "passive"))
      (node (ref "Q14") (pin "2") (pinfunction "2_2") (pintype "passive"))
      (node (ref "Q15") (pin "2") (pinfunction "2_2") (pintype "passive"))
      (node (ref "Q16") (pin "2") (pinfunction "2_2") (pintype "passive"))
      (node (ref "Q2") (pin "2") (pinfunction "2_2") (pintype "passive"))
      (node (ref "Q3") (pin "2") (pinfunction "2_2") (pintype "passive"))
      (node (ref "Q4") (pin "2") (pinfunction "2_2") (pintype "passive"))
      (node (ref "Q5") (pin "2") (pinfunction "2_2") (pintype "passive"))
      (node (ref "Q6") (pin "2") (pinfunction "2_2") (pintype "passive"))
      (node (ref "Q7") (pin "2") (pinfunction "2_2") (pintype "passive"))
      (node (ref "Q8") (pin "2") (pinfunction "2_2") (pintype "passive"))
      (node (ref "Q9") (pin "2") (pinfunction "2_2") (pintype "passive"))
      (node (ref "U9") (pin "4") (pinfunction "4_4") (pintype "passive"))
    )
    (net (code "23") (name "Net-(C18-Pad2)") (class "Default")
      (node (ref "C18") (pin "2") (pinfunction "2_2") (pintype "passive"))
      (node (ref "R17") (pin "2") (pinfunction "2_2") (pintype "passive"))
    )
    (net (code "24") (name "Net-(C19-Pad2)") (class "Default")
      (node (ref "C19") (pin "2") (pinfunction "2_2") (pintype "passive"))
      (node (ref "R20") (pin "2") (pinfunction "2_2") (pintype "passive"))
    )
    (net (code "25") (name "Net-(C20-Pad2)") (class "Default")
      (node (ref "C20") (pin "2") (pinfunction "2_2") (pintype "passive"))
      (node (ref "R28") (pin "2") (pinfunction "2_2") (pintype "passive"))
    )
    (net (code "26") (name "Net-(C21-Pad2)") (class "Default")
      (node (ref "C21") (pin "2") (pinfunction "2_2") (pintype "passive"))
      (node (ref "R31") (pin "2") (pinfunction "2_2") (pintype "passive"))
    )
    (net (code "27") (name "Net-(C22-Pad2)") (class "Default")
      (node (ref "C22") (pin "2") (pinfunction "2_2") (pintype "passive"))
      (node (ref "R36") (pin "2") (pinfunction "2_2") (pintype "passive"))
    )
    (net (code "28") (name "Net-(C23-Pad2)") (class "Default")
      (node (ref "C23") (pin "2") (pinfunction "2_2") (pintype "passive"))
      (node (ref "R39") (pin "2") (pinfunction "2_2") (pintype "passive"))
    )
    (net (code "29") (name "Net-(C24-Pad2)") (class "Default")
      (node (ref "C24") (pin "2") (pinfunction "2_2") (pintype "passive"))
      (node (ref "R42") (pin "2") (pinfunction "2_2") (pintype "passive"))
    )
    (net (code "30") (name "Net-(C25-Pad2)") (class "Default")
      (node (ref "C25") (pin "2") (pinfunction "2_2") (pintype "passive"))
      (node (ref "R48") (pin "2") (pinfunction "2_2") (pintype "passive"))
    )
    (net (code "31") (name "Net-(C26-Pad2)") (class "Default")
      (node (ref "C26") (pin "2") (pinfunction "2_2") (pintype "passive"))
      (node (ref "R52") (pin "2") (pinfunction "2_2") (pintype "passive"))
    )
    (net (code "32") (name "Net-(C27-Pad2)") (class "Default")
      (node (ref "C27") (pin "2") (pinfunction "2_2") (pintype "passive"))
      (node (ref "R54") (pin "2") (pinfunction "2_2") (pintype "passive"))
    )
    (net (code "33") (name "Net-(C28-Pad2)") (class "Default")
      (node (ref "C28") (pin "2") (pinfunction "2_2") (pintype "passive"))
      (node (ref "R55") (pin "2") (pinfunction "2_2") (pintype "passive"))
    )
    (net (code "34") (name "Net-(C29-Pad2)") (class "Default")
      (node (ref "C29") (pin "2") (pinfunction "2_2") (pintype "passive"))
      (node (ref "R56") (pin "2") (pinfunction "2_2") (pintype "passive"))
    )
    (net (code "35") (name "Net-(C30-Pad2)") (class "Default")
      (node (ref "C30") (pin "2") (pinfunction "2_2") (pintype "passive"))
      (node (ref "R57") (pin "2") (pinfunction "2_2") (pintype "passive"))
    )
    (net (code "36") (name "Net-(C31-Pad2)") (class "Default")
      (node (ref "C31") (pin "2") (pinfunction "2_2") (pintype "passive"))
      (node (ref "R58") (pin "2") (pinfunction "2_2") (pintype "passive"))
    )
    (net (code "37") (name "Net-(C32-Pad2)") (class "Default")
      (node (ref "C32") (pin "2") (pinfunction "2_2") (pintype "passive"))
      (node (ref "R62") (pin "2") (pinfunction "2_2") (pintype "passive"))
    )
    (net (code "38") (name "Net-(C33-Pad2)") (class "Default")
      (node (ref "C33") (pin "2") (pinfunction "2_2") (pintype "passive"))
      (node (ref "R63") (pin "2") (pinfunction "2_2") (pintype "passive"))
    )
    (net (code "39") (name "Net-(D4-+)") (class "Default")
      (node (ref "D4") (pin "1") (pinfunction "+_1") (pintype "passive"))
      (node (ref "R23") (pin "1") (pinfunction "2_1") (pintype "passive"))
    )
    (net (code "40") (name "Net-(D4--)") (class "Default")
      (node (ref "D4") (pin "2") (pinfunction "-_2") (pintype "passive"))
      (node (ref "U9") (pin "2") (pinfunction "2_2") (pintype "passive"))
    )
    (net (code "41") (name "Net-(D4-~_1)") (class "Default")
      (node (ref "D4") (pin "3") (pinfunction "~_1_3") (pintype "passive"))
      (node (ref "R24") (pin "2") (pinfunction "2_2") (pintype "passive"))
    )
    (net (code "42") (name "Net-(D4-~_2)") (class "Default")
      (node (ref "D4") (pin "4") (pinfunction "~_2_4") (pintype "passive"))
      (node (ref "R22") (pin "2") (pinfunction "2_2") (pintype "passive"))
    )
    (net (code "43") (name "Net-(Q1-Pad3)") (class "Default")
      (node (ref "Q1") (pin "3") (pinfunction "3_3") (pintype "passive"))
      (node (ref "U5") (pin "2") (pinfunction "2_2") (pintype "passive"))
    )
    (net (code "44") (name "Net-(Q2-Pad3)") (class "Default")
      (node (ref "Q2") (pin "3") (pinfunction "3_3") (pintype "passive"))
      (node (ref "U6") (pin "2") (pinfunction "2_2") (pintype "passive"))
    )
    (net (code "45") (name "Net-(Q3-Pad3)") (class "Default")
      (node (ref "Q3") (pin "3") (pinfunction "3_3") (pintype "passive"))
      (node (ref "U10") (pin "2") (pinfunction "2_2") (pintype "passive"))
    )
    (net (code "46") (name "Net-(Q4-Pad3)") (class "Default")
      (node (ref "Q4") (pin "3") (pinfunction "3_3") (pintype "passive"))
      (node (ref "U11") (pin "2") (pinfunction "2_2") (pintype "passive"))
    )
    (net (code "47") (name "Net-(Q5-Pad3)") (class "Default")
      (node (ref "Q5") (pin "3") (pinfunction "3_3") (pintype "passive"))
      (node (ref "U14") (pin "2") (pinfunction "2_2") (pintype "passive"))
    )
    (net (code "48") (name "Net-(Q6-Pad3)") (class "Default")
      (node (ref "Q6") (pin "3") (pinfunction "3_3") (pintype "passive"))
      (node (ref "U16") (pin "2") (pinfunction "2_2") (pintype "passive"))
    )
    (net (code "49") (name "Net-(Q7-Pad3)") (class "Default")
      (node (ref "Q7") (pin "3") (pinfunction "3_3") (pintype "passive"))
      (node (ref "U18") (pin "2") (pinfunction "2_2") (pintype "passive"))
    )
    (net (code "50") (name "Net-(Q8-Pad3)") (class "Default")
      (node (ref "Q8") (pin "3") (pinfunction "3_3") (pintype "passive"))
      (node (ref "U20") (pin "2") (pinfunction "2_2") (pintype "passive"))
    )
    (net (code "51") (name "Net-(Q9-Pad3)") (class "Default")
      (node (ref "Q9") (pin "3") (pinfunction "3_3") (pintype "passive"))
      (node (ref "U21") (pin "2") (pinfunction "2_2") (pintype "passive"))
    )
    (net (code "52") (name "Net-(Q10-Pad3)") (class "Default")
      (node (ref "Q10") (pin "3") (pinfunction "3_3") (pintype "passive"))
      (node (ref "U22") (pin "2") (pinfunction "2_2") (pintype "passive"))
    )
    (net (code "53") (name "Net-(Q11-Pad3)") (class "Default")
      (node (ref "Q11") (pin "3") (pinfunction "3_3") (pintype "passive"))
      (node (ref "U26") (pin "2") (pinfunction "2_2") (pintype "passive"))
    )
    (net (code "54") (name "Net-(Q12-Pad3)") (class "Default")
      (node (ref "Q12") (pin "3") (pinfunction "3_3") (pintype "passive"))
      (node (ref "U27") (pin "2") (pinfunction "2_2") (pintype "passive"))
    )
    (net (code "55") (name "Net-(Q13-Pad3)") (class "Default")
      (node (ref "Q13") (pin "3") (pinfunction "3_3") (pintype "passive"))
      (node (ref "U28") (pin "2") (pinfunction "2_2") (pintype "passive"))
    )
    (net (code "56") (name "Net-(Q14-Pad3)") (class "Default")
      (node (ref "Q14") (pin "3") (pinfunction "3_3") (pintype "passive"))
      (node (ref "U32") (pin "2") (pinfunction "2_2") (pintype "passive"))
    )
    (net (code "57") (name "Net-(Q15-Pad3)") (class "Default")
      (node (ref "Q15") (pin "3") (pinfunction "3_3") (pintype "passive"))
      (node (ref "U34") (pin "2") (pinfunction "2_2") (pintype "passive"))
    )
    (net (code "58") (name "Net-(Q16-Pad3)") (class "Default")
      (node (ref "Q16") (pin "3") (pinfunction "3_3") (pintype "passive"))
      (node (ref "U35") (pin "2") (pinfunction "2_2") (pintype "passive"))
    )
    (net (code "59") (name "Net-(R15-2)") (class "Default")
      (node (ref "R15") (pin "1") (pinfunction "2_1") (pintype "passive"))
      (node (ref "U5") (pin "1") (pinfunction "1_1") (pintype "passive"))
    )
    (net (code "60") (name "Net-(R16-2)") (class "Default")
      (node (ref "R16") (pin "1") (pinfunction "2_1") (pintype "passive"))
      (node (ref "U6") (pin "1") (pinfunction "1_1") (pintype "passive"))
    )
    (net (code "61") (name "Net-(R18-3)") (class "Default")
      (node (ref "R18") (pin "2") (pinfunction "3_2") (pintype "passive"))
      (node (ref "U5") (pin "6") (pinfunction "6_6") (pintype "passive"))
    )
    (net (code "62") (name "Net-(R21-3)") (class "Default")
      (node (ref "R21") (pin "2") (pinfunction "3_2") (pintype "passive"))
      (node (ref "U6") (pin "6") (pinfunction "6_6") (pintype "passive"))
    )
    (net (code "63") (name "Net-(R23-3)") (class "Default")
      (node (ref "R23") (pin "2") (pinfunction "3_2") (pintype "passive"))
      (node (ref "U9") (pin "1") (pinfunction "1_1") (pintype "passive"))
    )
    (net (code "64") (name "Net-(R25-3)") (class "Default")
      (node (ref "R25") (pin "2") (pinfunction "3_2") (pintype "passive"))
      (node (ref "U10") (pin "6") (pinfunction "6_6") (pintype "passive"))
    )
    (net (code "65") (name "Net-(R26-3)") (class "Default")
      (node (ref "R26") (pin "2") (pinfunction "3_2") (pintype "passive"))
      (node (ref "U11") (pin "6") (pinfunction "6_6") (pintype "passive"))
    )
    (net (code "66") (name "Net-(R27-2)") (class "Default")
      (node (ref "R27") (pin "1") (pinfunction "2_1") (pintype "passive"))
      (node (ref "U10") (pin "1") (pinfunction "1_1") (pintype "passive"))
    )
    (net (code "67") (name "Net-(R29-3)") (class "Default")
      (node (ref "R29") (pin "2") (pinfunction "3_2") (pintype "passive"))
      (node (ref "U14") (pin "6") (pinfunction "6_6") (pintype "passive"))
    )
    (net (code "68") (name "Net-(R30-2)") (class "Default")
      (node (ref "R30") (pin "1") (pinfunction "2_1") (pintype "passive"))
      (node (ref "U11") (pin "1") (pinfunction "1_1") (pintype "passive"))
    )
    (net (code "69") (name "Net-(R32-3)") (class "Default")
      (node (ref "R32") (pin "2") (pinfunction "3_2") (pintype "passive"))
      (node (ref "U16") (pin "6") (pinfunction "6_6") (pintype "passive"))
    )
    (net (code "70") (name "Net-(R33-3)") (class "Default")
      (node (ref "R33") (pin "2") (pinfunction "3_2") (pintype "passive"))
      (node (ref "U18") (pin "6") (pinfunction "6_6") (pintype "passive"))
    )
    (net (code "71") (name "Net-(R34-3)") (class "Default")
      (node (ref "R34") (pin "2") (pinfunction "3_2") (pintype "passive"))
      (node (ref "U20") (pin "6") (pinfunction "6_6") (pintype "passive"))
    )
    (net (code "72") (name "Net-(R35-2)") (class "Default")
      (node (ref "R35") (pin "1") (pinfunction "2_1") (pintype "passive"))
      (node (ref "U14") (pin "1") (pinfunction "1_1") (pintype "passive"))
    )
    (net (code "73") (name "Net-(R37-3)") (class "Default")
      (node (ref "R37") (pin "2") (pinfunction "3_2") (pintype "passive"))
      (node (ref "U21") (pin "6") (pinfunction "6_6") (pintype "passive"))
    )
    (net (code "74") (name "Net-(R38-2)") (class "Default")
      (node (ref "R38") (pin "1") (pinfunction "2_1") (pintype "passive"))
      (node (ref "U16") (pin "1") (pinfunction "1_1") (pintype "passive"))
    )
    (net (code "75") (name "Net-(R40-3)") (class "Default")
      (node (ref "R40") (pin "2") (pinfunction "3_2") (pintype "passive"))
      (node (ref "U22") (pin "6") (pinfunction "6_6") (pintype "passive"))
    )
    (net (code "76") (name "Net-(R41-2)") (class "Default")
      (node (ref "R41") (pin "1") (pinfunction "2_1") (pintype "passive"))
      (node (ref "U18") (pin "1") (pinfunction "1_1") (pintype "passive"))
    )
    (net (code "77") (name "Net-(R43-3)") (class "Default")
      (node (ref "R43") (pin "2") (pinfunction "3_2") (pintype "passive"))
      (node (ref "U26") (pin "6") (pinfunction "6_6") (pintype "passive"))
    )
    (net (code "78") (name "Net-(R44-3)") (class "Default")
      (node (ref "R44") (pin "2") (pinfunction "3_2") (pintype "passive"))
      (node (ref "U27") (pin "6") (pinfunction "6_6") (pintype "passive"))
    )
    (net (code "79") (name "Net-(R45-3)") (class "Default")
      (node (ref "R45") (pin "2") (pinfunction "3_2") (pintype "passive"))
      (node (ref "U28") (pin "6") (pinfunction "6_6") (pintype "passive"))
    )
    (net (code "80") (name "Net-(R46-3)") (class "Default")
      (node (ref "R46") (pin "2") (pinfunction "3_2") (pintype "passive"))
      (node (ref "U32") (pin "6") (pinfunction "6_6") (pintype "passive"))
    )
    (net (code "81") (name "Net-(R47-2)") (class "Default")
      (node (ref "R47") (pin "1") (pinfunction "2_1") (pintype "passive"))
      (node (ref "U20") (pin "1") (pinfunction "1_1") (pintype "passive"))
    )
    (net (code "82") (name "Net-(R49-3)") (class "Default")
      (node (ref "R49") (pin "2") (pinfunction "3_2") (pintype "passive"))
      (node (ref "U34") (pin "6") (pinfunction "6_6") (pintype "passive"))
    )
    (net (code "83") (name "Net-(R50-2)") (class "Default")
      (node (ref "R50") (pin "1") (pinfunction "2_1") (pintype "passive"))
      (node (ref "U21") (pin "1") (pinfunction "1_1") (pintype "passive"))
    )
    (net (code "84") (name "Net-(R51-2)") (class "Default")
      (node (ref "R51") (pin "1") (pinfunction "2_1") (pintype "passive"))
      (node (ref "U22") (pin "1") (pinfunction "1_1") (pintype "passive"))
    )
    (net (code "85") (name "Net-(R53-3)") (class "Default")
      (node (ref "R53") (pin "2") (pinfunction "3_2") (pintype "passive"))
      (node (ref "U35") (pin "6") (pinfunction "6_6") (pintype "passive"))
    )
    (net (code "86") (name "Net-(R59-2)") (class "Default")
      (node (ref "R59") (pin "1") (pinfunction "2_1") (pintype "passive"))
      (node (ref "U26") (pin "1") (pinfunction "1_1") (pintype "passive"))
    )
    (net (code "87") (name "Net-(R60-2)") (class "Default")
      (node (ref "R60") (pin "1") (pinfunction "2_1") (pintype "passive"))
      (node (ref "U27") (pin "1") (pinfunction "1_1") (pintype "passive"))
    )
    (net (code "88") (name "Net-(R61-2)") (class "Default")
      (node (ref "R61") (pin "1") (pinfunction "2_1") (pintype "passive"))
      (node (ref "U28") (pin "1") (pinfunction "1_1") (pintype "passive"))
    )
    (net (code "89") (name "Net-(R71-2)") (class "Default")
      (node (ref "R71") (pin "1") (pinfunction "2_1") (pintype "passive"))
      (node (ref "U32") (pin "1") (pinfunction "1_1") (pintype "passive"))
    )
    (net (code "90") (name "Net-(R74-2)") (class "Default")
      (node (ref "R74") (pin "1") (pinfunction "2_1") (pintype "passive"))
      (node (ref "U34") (pin "1") (pinfunction "1_1") (pintype "passive"))
    )
    (net (code "91") (name "Net-(R77-2)") (class "Default")
      (node (ref "R77") (pin "1") (pinfunction "2_1") (pintype "passive"))
      (node (ref "U35") (pin "1") (pinfunction "1_1") (pintype "passive"))
    )
    (net (code "92") (name "Net-(U7-A1)") (class "Default")
      (node (ref "C18") (pin "1") (pinfunction "1_1") (pintype "passive"))
      (node (ref "J8") (pin "1") (pinfunction "1_1") (pintype "passive"))
      (node (ref "U7") (pin "1") (pinfunction "A1_1") (pintype "passive"))
    )
    (net (code "93") (name "Net-(U7-G)") (class "Default")
      (node (ref "U5") (pin "4") (pinfunction "4_4") (pintype "passive"))
      (node (ref "U7") (pin "3") (pinfunction "G_3") (pintype "passive"))
    )
    (net (code "94") (name "Net-(U8-A1)") (class "Default")
      (node (ref "C19") (pin "1") (pinfunction "1_1") (pintype "passive"))
      (node (ref "J9") (pin "1") (pinfunction "1_1") (pintype "passive"))
      (node (ref "U8") (pin "1") (pinfunction "A1_1") (pintype "passive"))
    )
    (net (code "95") (name "Net-(U8-G)") (class "Default")
      (node (ref "U6") (pin "4") (pinfunction "4_4") (pintype "passive"))
      (node (ref "U8") (pin "3") (pinfunction "G_3") (pintype "passive"))
    )
    (net (code "96") (name "Net-(U12-A1)") (class "Default")
      (node (ref "C20") (pin "1") (pinfunction "1_1") (pintype "passive"))
      (node (ref "J10") (pin "1") (pinfunction "1_1") (pintype "passive"))
      (node (ref "U12") (pin "1") (pinfunction "A1_1") (pintype "passive"))
    )
    (net (code "97") (name "Net-(U12-G)") (class "Default")
      (node (ref "U10") (pin "4") (pinfunction "4_4") (pintype "passive"))
      (node (ref "U12") (pin "3") (pinfunction "G_3") (pintype "passive"))
    )
    (net (code "98") (name "Net-(U13-A1)") (class "Default")
      (node (ref "C21") (pin "1") (pinfunction "1_1") (pintype "passive"))
      (node (ref "J11") (pin "1") (pinfunction "1_1") (pintype "passive"))
      (node (ref "U13") (pin "1") (pinfunction "A1_1") (pintype "passive"))
    )
    (net (code "99") (name "Net-(U13-G)") (class "Default")
      (node (ref "U11") (pin "4") (pinfunction "4_4") (pintype "passive"))
      (node (ref "U13") (pin "3") (pinfunction "G_3") (pintype "passive"))
    )
    (net (code "100") (name "Net-(U15-A1)") (class "Default")
      (node (ref "C22") (pin "1") (pinfunction "1_1") (pintype "passive"))
      (node (ref "J12") (pin "1") (pinfunction "1_1") (pintype "passive"))
      (node (ref "U15") (pin "1") (pinfunction "A1_1") (pintype "passive"))
    )
    (net (code "101") (name "Net-(U15-G)") (class "Default")
      (node (ref "U14") (pin "4") (pinfunction "4_4") (pintype "passive"))
      (node (ref "U15") (pin "3") (pinfunction "G_3") (pintype "passive"))
    )
    (net (code "102") (name "Net-(U17-A1)") (class "Default")
      (node (ref "C23") (pin "1") (pinfunction "1_1") (pintype "passive"))
      (node (ref "J13") (pin "1") (pinfunction "1_1") (pintype "passive"))
      (node (ref "U17") (pin "1") (pinfunction "A1_1") (pintype "passive"))
    )
    (net (code "103") (name "Net-(U17-G)") (class "Default")
      (node (ref "U16") (pin "4") (pinfunction "4_4") (pintype "passive"))
      (node (ref "U17") (pin "3") (pinfunction "G_3") (pintype "passive"))
    )
    (net (code "104") (name "Net-(U19-A1)") (class "Default")
      (node (ref "C24") (pin "1") (pinfunction "1_1") (pintype "passive"))
      (node (ref "J14") (pin "1") (pinfunction "1_1") (pintype "passive"))
      (node (ref "U19") (pin "1") (pinfunction "A1_1") (pintype "passive"))
    )
    (net (code "105") (name "Net-(U19-G)") (class "Default")
      (node (ref "U18") (pin "4") (pinfunction "4_4") (pintype "passive"))
      (node (ref "U19") (pin "3") (pinfunction "G_3") (pintype "passive"))
    )
    (net (code "106") (name "Net-(U23-A1)") (class "Default")
      (node (ref "C25") (pin "1") (pinfunction "1_1") (pintype "passive"))
      (node (ref "J15") (pin "1") (pinfunction "1_1") (pintype "passive"))
      (node (ref "U23") (pin "1") (pinfunction "A1_1") (pintype "passive"))
    )
    (net (code "107") (name "Net-(U23-G)") (class "Default")
      (node (ref "U20") (pin "4") (pinfunction "4_4") (pintype "passive"))
      (node (ref "U23") (pin "3") (pinfunction "G_3") (pintype "passive"))
    )
    (net (code "108") (name "Net-(U24-A1)") (class "Default")
      (node (ref "C26") (pin "1") (pinfunction "1_1") (pintype "passive"))
      (node (ref "J16") (pin "1") (pinfunction "1_1") (pintype "passive"))
      (node (ref "U24") (pin "1") (pinfunction "A1_1") (pintype "passive"))
    )
    (net (code "109") (name "Net-(U24-G)") (class "Default")
      (node (ref "U21") (pin "4") (pinfunction "4_4") (pintype "passive"))
      (node (ref "U24") (pin "3") (pinfunction "G_3") (pintype "passive"))
    )
    (net (code "110") (name "Net-(U25-A1)") (class "Default")
      (node (ref "C27") (pin "1") (pinfunction "1_1") (pintype "passive"))
      (node (ref "J17") (pin "1") (pinfunction "1_1") (pintype "passive"))
      (node (ref "U25") (pin "1") (pinfunction "A1_1") (pintype "passive"))
    )
    (net (code "111") (name "Net-(U25-G)") (class "Default")
      (node (ref "U22") (pin "4") (pinfunction "4_4") (pintype "passive"))
      (node (ref "U25") (pin "3") (pinfunction "G_3") (pintype "passive"))
    )
    (net (code "112") (name "Net-(U29-A1)") (class "Default")
      (node (ref "C28") (pin "1") (pinfunction "1_1") (pintype "passive"))
      (node (ref "J18") (pin "1") (pinfunction "1_1") (pintype "passive"))
      (node (ref "U29") (pin "1") (pinfunction "A1_1") (pintype "passive"))
    )
    (net (code "113") (name "Net-(U29-G)") (class "Default")
      (node (ref "U26") (pin "4") (pinfunction "4_4") (pintype "passive"))
      (node (ref "U29") (pin "3") (pinfunction "G_3") (pintype "passive"))
    )
    (net (code "114") (name "Net-(U30-A1)") (class "Default")
      (node (ref "C29") (pin "1") (pinfunction "1_1") (pintype "passive"))
      (node (ref "J19") (pin "1") (pinfunction "1_1") (pintype "passive"))
      (node (ref "U30") (pin "1") (pinfunction "A1_1") (pintype "passive"))
    )
    (net (code "115") (name "Net-(U30-G)") (class "Default")
      (node (ref "U27") (pin "4") (pinfunction "4_4") (pintype "passive"))
      (node (ref "U30") (pin "3") (pinfunction "G_3") (pintype "passive"))
    )
    (net (code "116") (name "Net-(U31-A1)") (class "Default")
      (node (ref "C30") (pin "1") (pinfunction "1_1") (pintype "passive"))
      (node (ref "J20") (pin "1") (pinfunction "1_1") (pintype "passive"))
      (node (ref "U31") (pin "1") (pinfunction "A1_1") (pintype "passive"))
    )
    (net (code "117") (name "Net-(U31-G)") (class "Default")
      (node (ref "U28") (pin "4") (pinfunction "4_4") (pintype "passive"))
      (node (ref "U31") (pin "3") (pinfunction "G_3") (pintype "passive"))
    )
    (net (code "118") (name "Net-(U33-A1)") (class "Default")
      (node (ref "C31") (pin "1") (pinfunction "1_1") (pintype "passive"))
      (node (ref "J21") (pin "1") (pinfunction "1_1") (pintype "passive"))
      (node (ref "U33") (pin "1") (pinfunction "A1_1") (pintype "passive"))
    )
    (net (code "119") (name "Net-(U33-G)") (class "Default")
      (node (ref "U32") (pin "4") (pinfunction "4_4") (pintype "passive"))
      (node (ref "U33") (pin "3") (pinfunction "G_3") (pintype "passive"))
    )
    (net (code "120") (name "Net-(U36-A1)") (class "Default")
      (node (ref "C32") (pin "1") (pinfunction "1_1") (pintype "passive"))
      (node (ref "J22") (pin "1") (pinfunction "1_1") (pintype "passive"))
      (node (ref "U36") (pin "1") (pinfunction "A1_1") (pintype "passive"))
    )
    (net (code "121") (name "Net-(U36-G)") (class "Default")
      (node (ref "U34") (pin "4") (pinfunction "4_4") (pintype "passive"))
      (node (ref "U36") (pin "3") (pinfunction "G_3") (pintype "passive"))
    )
    (net (code "122") (name "Net-(U37-A1)") (class "Default")
      (node (ref "C33") (pin "1") (pinfunction "1_1") (pintype "passive"))
      (node (ref "J23") (pin "1") (pinfunction "1_1") (pintype "passive"))
      (node (ref "U37") (pin "1") (pinfunction "A1_1") (pintype "passive"))
    )
    (net (code "123") (name "Net-(U37-G)") (class "Default")
      (node (ref "U35") (pin "4") (pinfunction "4_4") (pintype "passive"))
      (node (ref "U37") (pin "3") (pinfunction "G_3") (pintype "passive"))
    )
    (net (code "124") (name "unconnected-(U5-Pad3)") (class "Default")
      (node (ref "U5") (pin "3") (pinfunction "3_3") (pintype "passive"))
    )
    (net (code "125") (name "unconnected-(U5-Pad5)") (class "Default")
      (node (ref "U5") (pin "5") (pinfunction "5_5") (pintype "passive"))
    )
    (net (code "126") (name "unconnected-(U6-Pad3)") (class "Default")
      (node (ref "U6") (pin "3") (pinfunction "3_3") (pintype "passive"))
    )
    (net (code "127") (name "unconnected-(U6-Pad5)") (class "Default")
      (node (ref "U6") (pin "5") (pinfunction "5_5") (pintype "passive"))
    )
    (net (code "128") (name "unconnected-(U9-Pad3)") (class "Default")
      (node (ref "U9") (pin "3") (pinfunction "3_3") (pintype "passive"))
    )
    (net (code "129") (name "unconnected-(U9-Pad6)") (class "Default")
      (node (ref "U9") (pin "6") (pinfunction "6_6") (pintype "passive"))
    )
    (net (code "130") (name "unconnected-(U10-Pad3)") (class "Default")
      (node (ref "U10") (pin "3") (pinfunction "3_3") (pintype "passive"))
    )
    (net (code "131") (name "unconnected-(U10-Pad5)") (class "Default")
      (node (ref "U10") (pin "5") (pinfunction "5_5") (pintype "passive"))
    )
    (net (code "132") (name "unconnected-(U11-Pad3)") (class "Default")
      (node (ref "U11") (pin "3") (pinfunction "3_3") (pintype "passive"))
    )
    (net (code "133") (name "unconnected-(U11-Pad5)") (class "Default")
      (node (ref "U11") (pin "5") (pinfunction "5_5") (pintype "passive"))
    )
    (net (code "134") (name "unconnected-(U14-Pad3)") (class "Default")
      (node (ref "U14") (pin "3") (pinfunction "3_3") (pintype "passive"))
    )
    (net (code "135") (name "unconnected-(U14-Pad5)") (class "Default")
      (node (ref "U14") (pin "5") (pinfunction "5_5") (pintype "passive"))
    )
    (net (code "136") (name "unconnected-(U16-Pad3)") (class "Default")
      (node (ref "U16") (pin "3") (pinfunction "3_3") (pintype "passive"))
    )
    (net (code "137") (name "unconnected-(U16-Pad5)") (class "Default")
      (node (ref "U16") (pin "5") (pinfunction "5_5") (pintype "passive"))
    )
    (net (code "138") (name "unconnected-(U18-Pad3)") (class "Default")
      (node (ref "U18") (pin "3") (pinfunction "3_3") (pintype "passive"))
    )
    (net (code "139") (name "unconnected-(U18-Pad5)") (class "Default")
      (node (ref "U18") (pin "5") (pinfunction "5_5") (pintype "passive"))
    )
    (net (code "140") (name "unconnected-(U20-Pad3)") (class "Default")
      (node (ref "U20") (pin "3") (pinfunction "3_3") (pintype "passive"))
    )
    (net (code "141") (name "unconnected-(U20-Pad5)") (class "Default")
      (node (ref "U20") (pin "5") (pinfunction "5_5") (pintype "passive"))
    )
    (net (code "142") (name "unconnected-(U21-Pad3)") (class "Default")
      (node (ref "U21") (pin "3") (pinfunction "3_3") (pintype "passive"))
    )
    (net (code "143") (name "unconnected-(U21-Pad5)") (class "Default")
      (node (ref "U21") (pin "5") (pinfunction "5_5") (pintype "passive"))
    )
    (net (code "144") (name "unconnected-(U22-Pad3)") (class "Default")
      (node (ref "U22") (pin "3") (pinfunction "3_3") (pintype "passive"))
    )
    (net (code "145") (name "unconnected-(U22-Pad5)") (class "Default")
      (node (ref "U22") (pin "5") (pinfunction "5_5") (pintype "passive"))
    )
    (net (code "146") (name "unconnected-(U26-Pad3)") (class "Default")
      (node (ref "U26") (pin "3") (pinfunction "3_3") (pintype "passive"))
    )
    (net (code "147") (name "unconnected-(U26-Pad5)") (class "Default")
      (node (ref "U26") (pin "5") (pinfunction "5_5") (pintype "passive"))
    )
    (net (code "148") (name "unconnected-(U27-Pad3)") (class "Default")
      (node (ref "U27") (pin "3") (pinfunction "3_3") (pintype "passive"))
    )
    (net (code "149") (name "unconnected-(U27-Pad5)") (class "Default")
      (node (ref "U27") (pin "5") (pinfunction "5_5") (pintype "passive"))
    )
    (net (code "150") (name "unconnected-(U28-Pad3)") (class "Default")
      (node (ref "U28") (pin "3") (pinfunction "3_3") (pintype "passive"))
    )
    (net (code "151") (name "unconnected-(U28-Pad5)") (class "Default")
      (node (ref "U28") (pin "5") (pinfunction "5_5") (pintype "passive"))
    )
    (net (code "152") (name "unconnected-(U32-Pad3)") (class "Default")
      (node (ref "U32") (pin "3") (pinfunction "3_3") (pintype "passive"))
    )
    (net (code "153") (name "unconnected-(U32-Pad5)") (class "Default")
      (node (ref "U32") (pin "5") (pinfunction "5_5") (pintype "passive"))
    )
    (net (code "154") (name "unconnected-(U34-Pad3)") (class "Default")
      (node (ref "U34") (pin "3") (pinfunction "3_3") (pintype "passive"))
    )
    (net (code "155") (name "unconnected-(U34-Pad5)") (class "Default")
      (node (ref "U34") (pin "5") (pinfunction "5_5") (pintype "passive"))
    )
    (net (code "156") (name "unconnected-(U35-Pad3)") (class "Default")
      (node (ref "U35") (pin "3") (pinfunction "3_3") (pintype "passive"))
    )
    (net (code "157") (name "unconnected-(U35-Pad5)") (class "Default")
      (node (ref "U35") (pin "5") (pinfunction "5_5") (pintype "passive"))
    )
  )
)
